# seletor.net
KiCad netlist of a schematic drawn in EAGLE
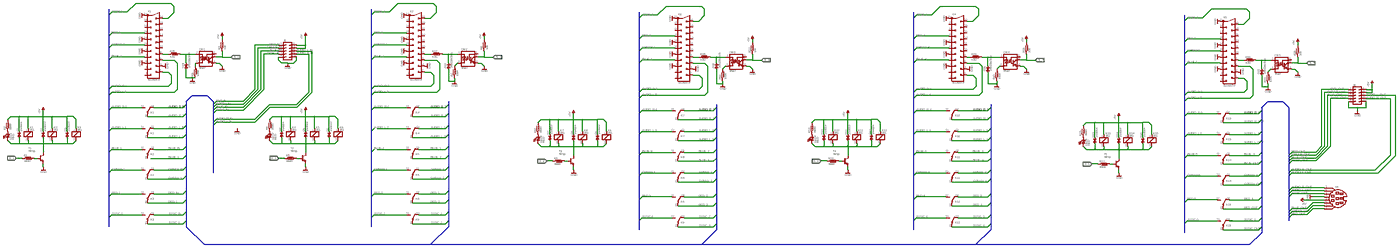
[diagram p0: schematic, sheet 1, overview]
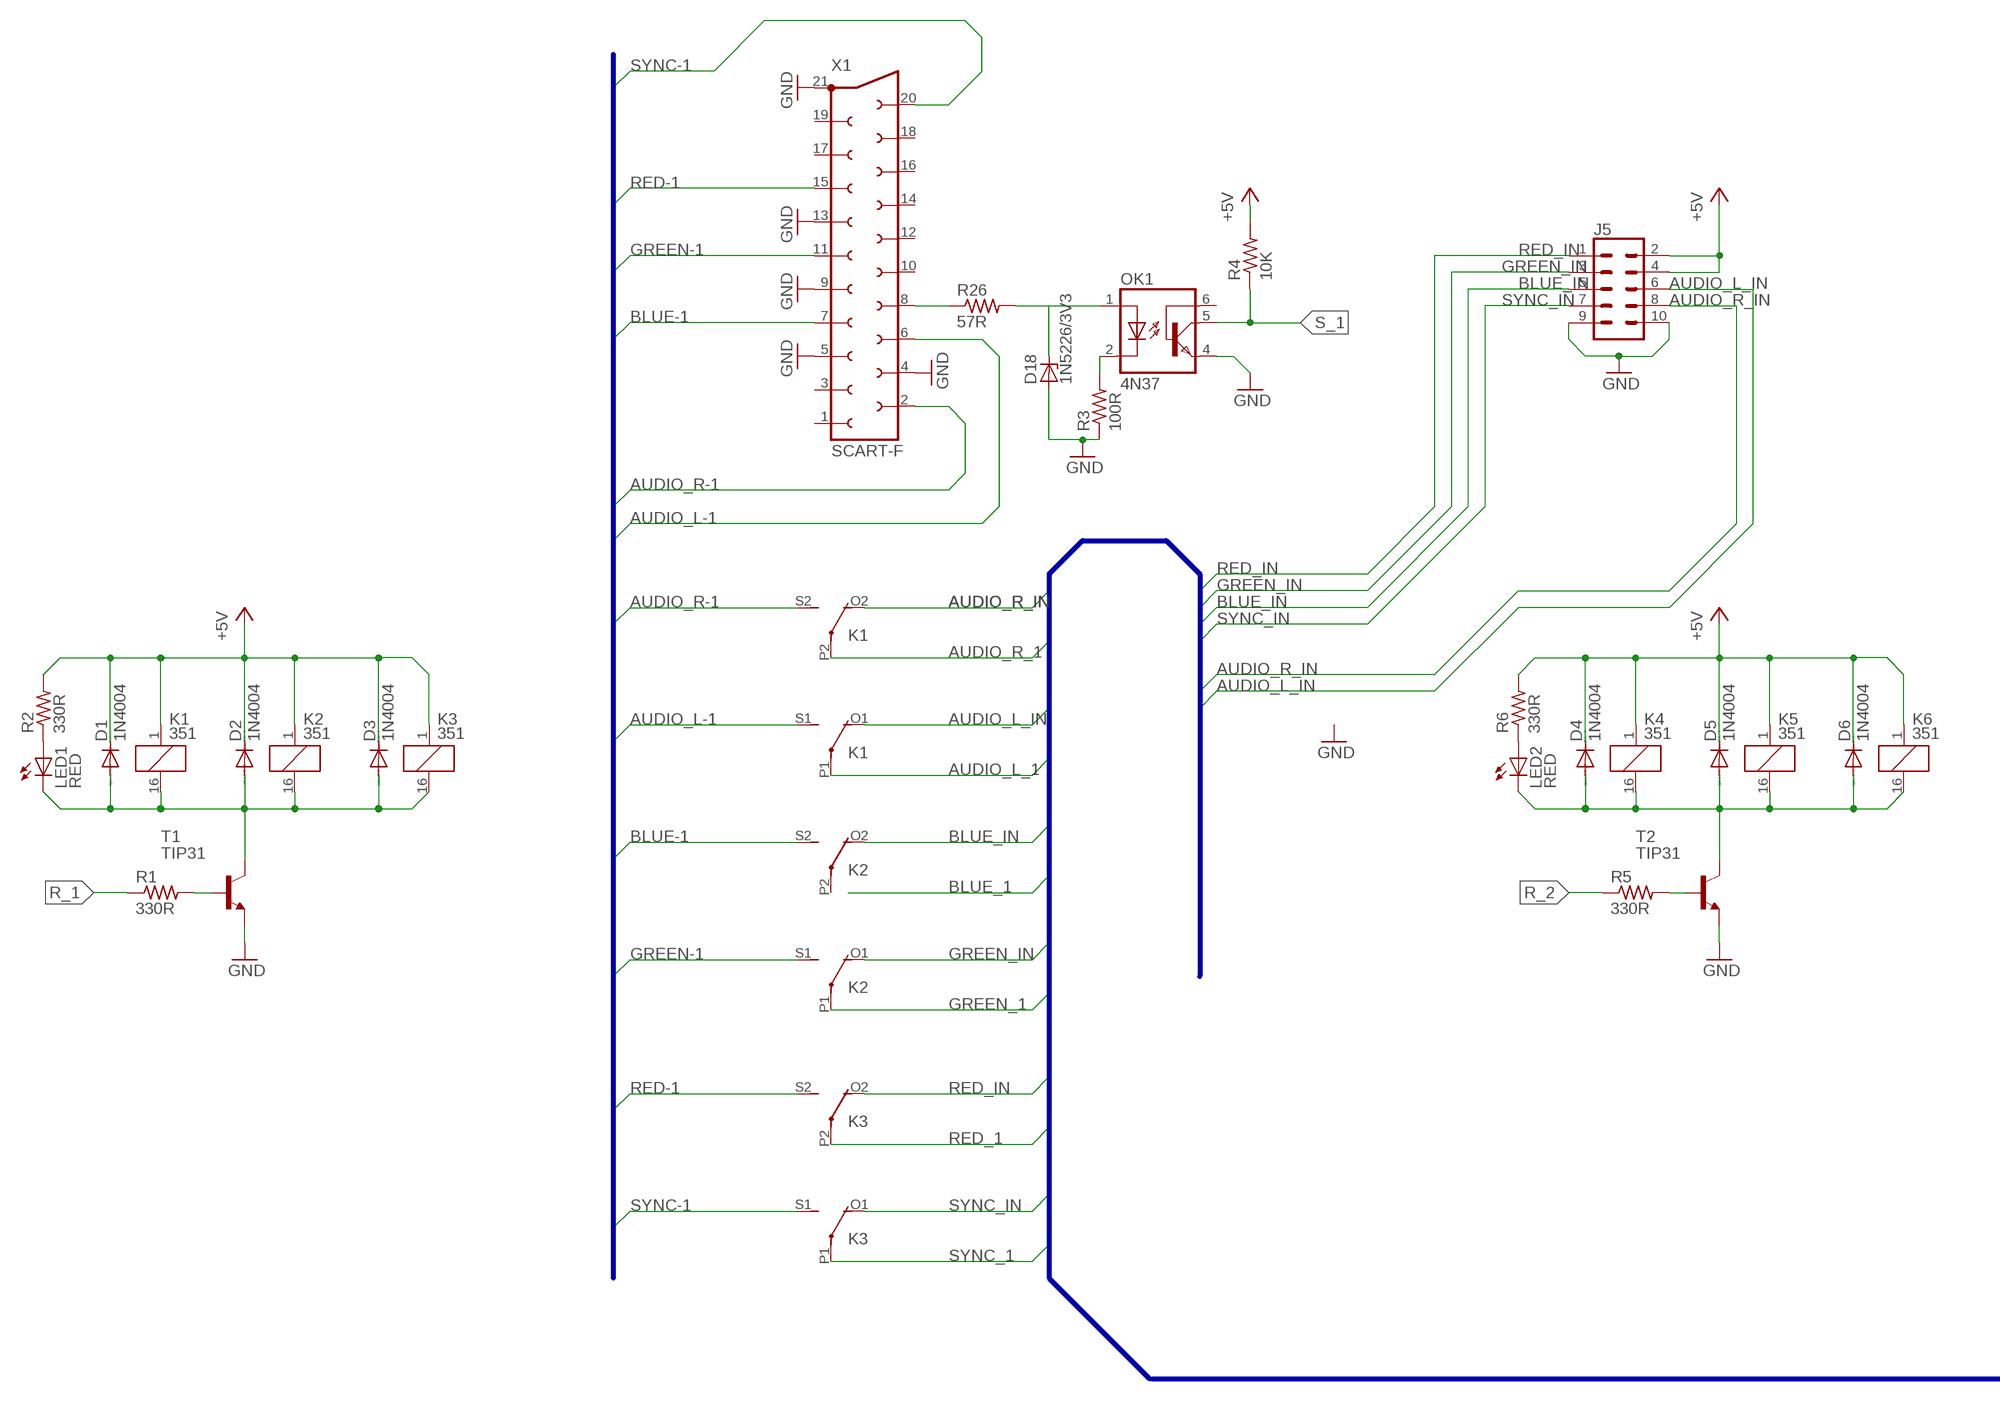
[diagram p1: schematic, sheet 1, part 1 of 4]
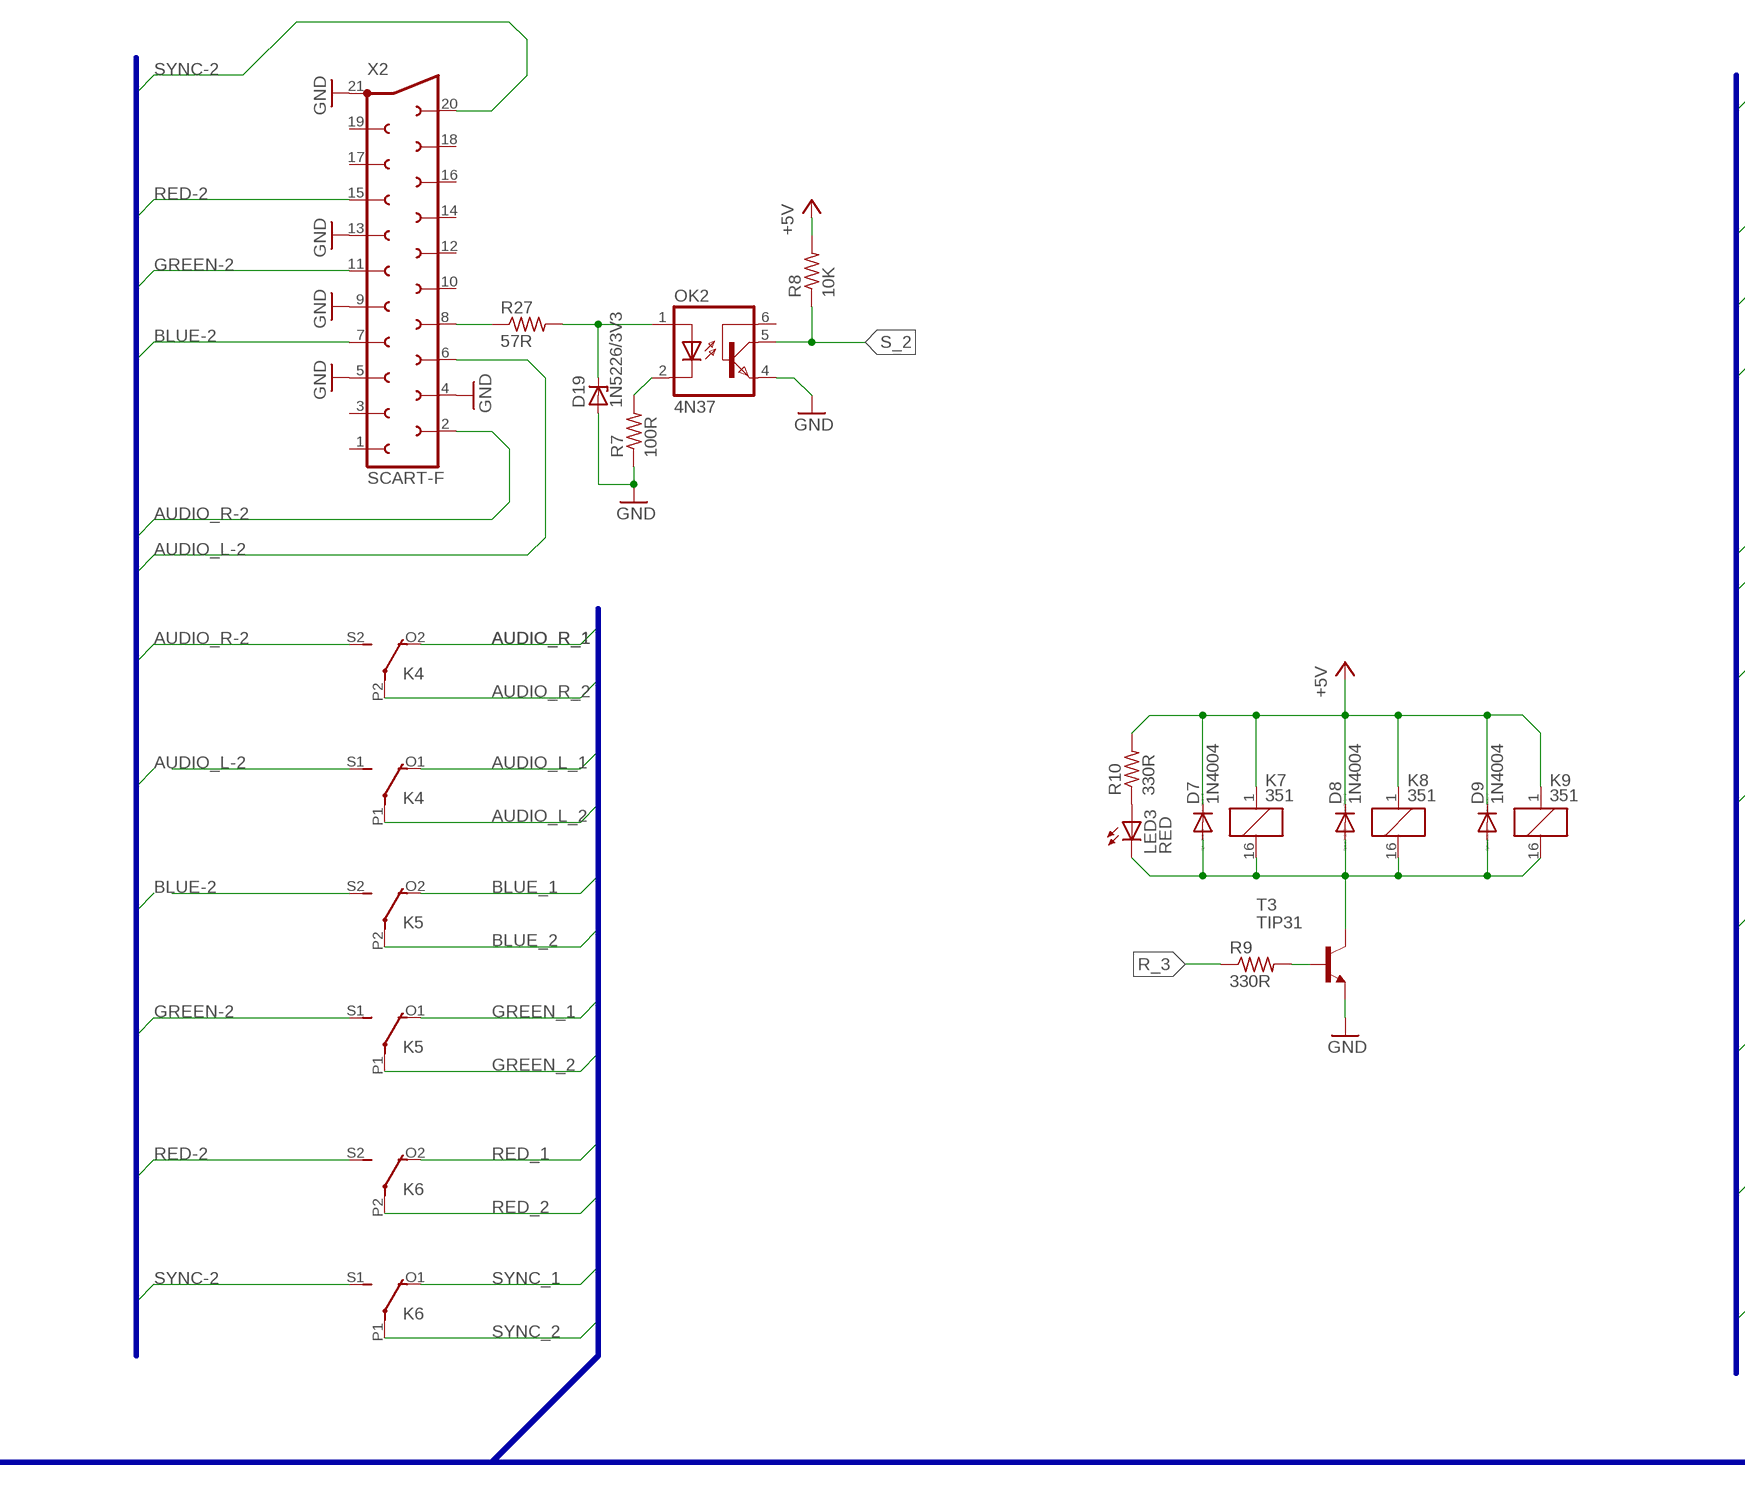
[diagram p2: schematic, sheet 1, part 2 of 4]
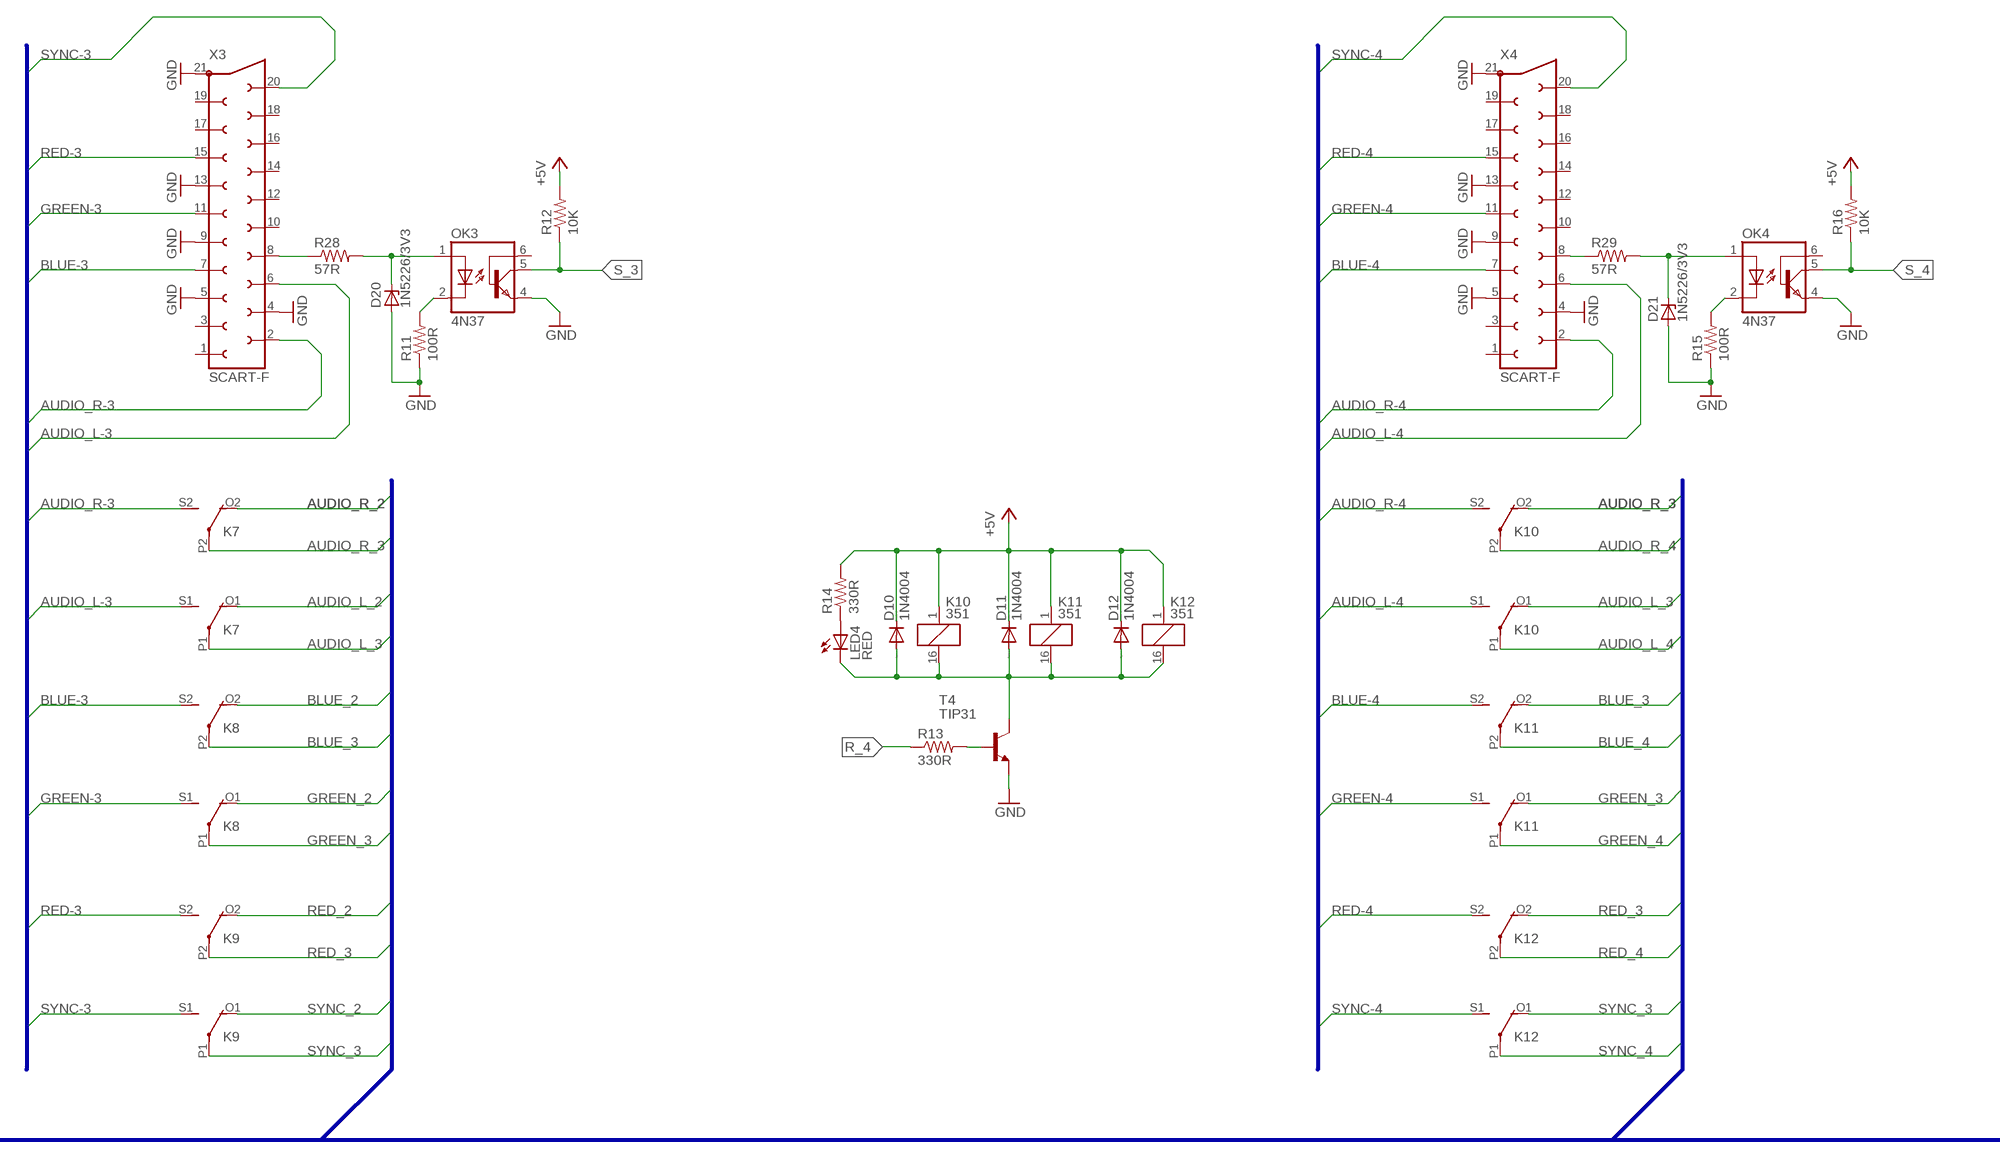
[diagram p3: schematic, sheet 1, part 3 of 4]
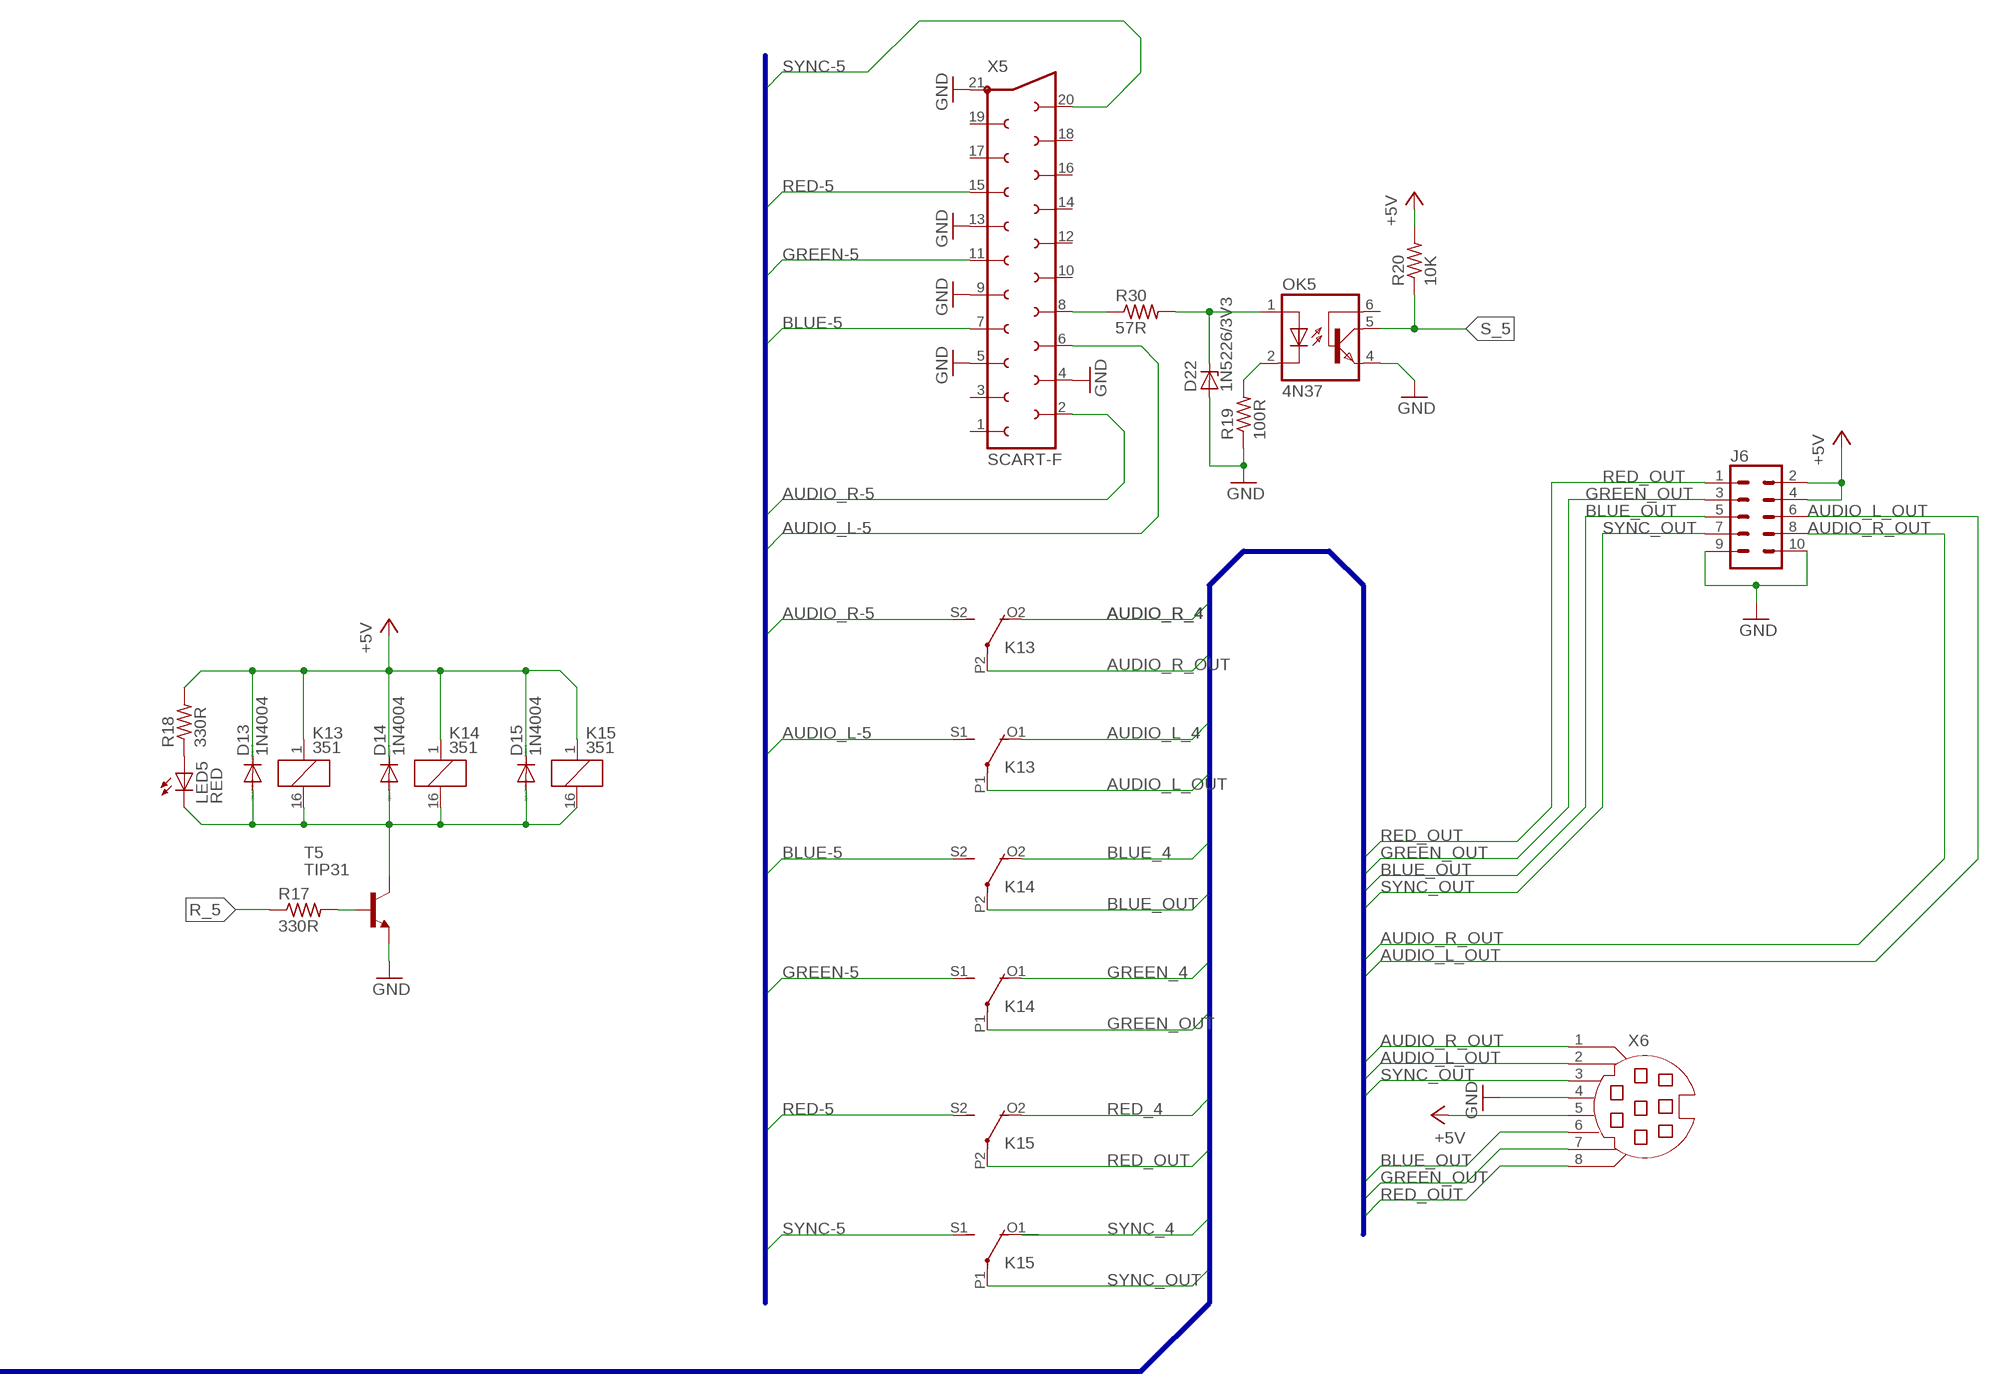
[diagram p4: schematic, sheet 1, part 4 of 4]
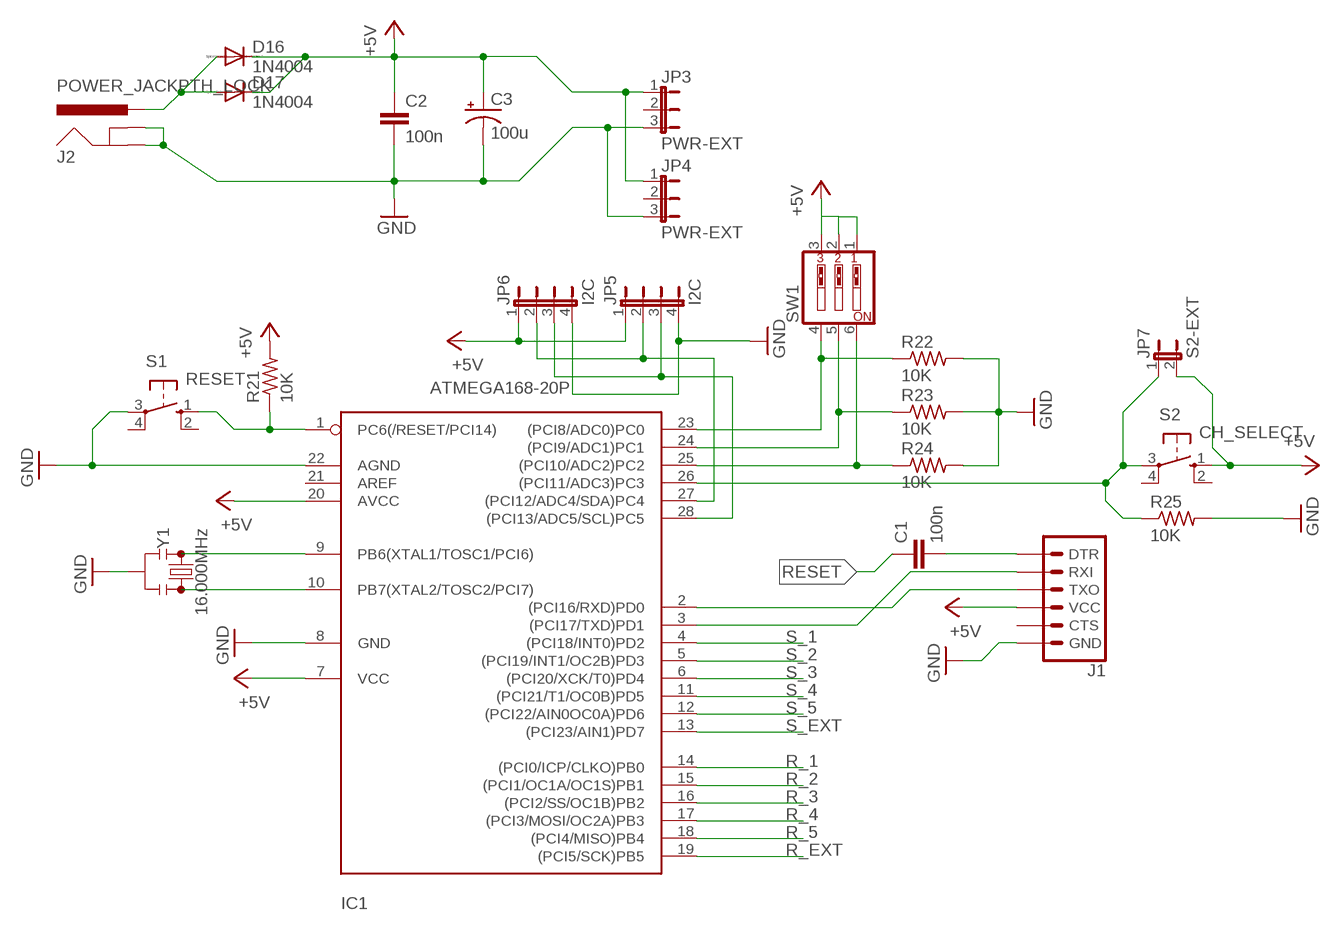
[diagram p5: schematic, sheet 2]

(export (version "E")
  (design (tool "Eeschema 10.0.6"))
  (components
    (comp (ref "D1")
      (value "1N4004")
      (footprint "eagle-import:DO41-10")
      (libsource (lib "eagle-import") (part "1N4004"))
    )
    (comp (ref "D2")
      (value "1N4004")
      (footprint "eagle-import:DO41-10")
      (libsource (lib "eagle-import") (part "1N4004"))
    )
    (comp (ref "D3")
      (value "1N4004")
      (footprint "eagle-import:DO41-10")
      (libsource (lib "eagle-import") (part "1N4004"))
    )
    (comp (ref "D4")
      (value "1N4004")
      (footprint "eagle-import:DO41-10")
      (libsource (lib "eagle-import") (part "1N4004"))
    )
    (comp (ref "D5")
      (value "1N4004")
      (footprint "eagle-import:DO41-10")
      (libsource (lib "eagle-import") (part "1N4004"))
    )
    (comp (ref "D6")
      (value "1N4004")
      (footprint "eagle-import:DO41-10")
      (libsource (lib "eagle-import") (part "1N4004"))
    )
    (comp (ref "D7")
      (value "1N4004")
      (footprint "eagle-import:DO41-10")
      (libsource (lib "eagle-import") (part "1N4004"))
    )
    (comp (ref "D8")
      (value "1N4004")
      (footprint "eagle-import:DO41-10")
      (libsource (lib "eagle-import") (part "1N4004"))
    )
    (comp (ref "D9")
      (value "1N4004")
      (footprint "eagle-import:DO41-10")
      (libsource (lib "eagle-import") (part "1N4004"))
    )
    (comp (ref "D10")
      (value "1N4004")
      (footprint "eagle-import:DO41-10")
      (libsource (lib "eagle-import") (part "1N4004"))
    )
    (comp (ref "D11")
      (value "1N4004")
      (footprint "eagle-import:DO41-10")
      (libsource (lib "eagle-import") (part "1N4004"))
    )
    (comp (ref "D12")
      (value "1N4004")
      (footprint "eagle-import:DO41-10")
      (libsource (lib "eagle-import") (part "1N4004"))
    )
    (comp (ref "D13")
      (value "1N4004")
      (footprint "eagle-import:DO41-10")
      (libsource (lib "eagle-import") (part "1N4004"))
    )
    (comp (ref "D14")
      (value "1N4004")
      (footprint "eagle-import:DO41-10")
      (libsource (lib "eagle-import") (part "1N4004"))
    )
    (comp (ref "D15")
      (value "1N4004")
      (footprint "eagle-import:DO41-10")
      (libsource (lib "eagle-import") (part "1N4004"))
    )
    (comp (ref "D18")
      (value "1N5226/3V3")
      (footprint "eagle-import:DO34Z7")
      (libsource (lib "eagle-import") (part "BZV10"))
    )
    (comp (ref "D19")
      (value "1N5226/3V3")
      (footprint "eagle-import:DO34Z7")
      (libsource (lib "eagle-import") (part "BZV10"))
    )
    (comp (ref "D20")
      (value "1N5226/3V3")
      (footprint "eagle-import:DO34Z7")
      (libsource (lib "eagle-import") (part "BZV10"))
    )
    (comp (ref "D21")
      (value "1N5226/3V3")
      (footprint "eagle-import:DO34Z7")
      (libsource (lib "eagle-import") (part "BZV10"))
    )
    (comp (ref "D22")
      (value "1N5226/3V3")
      (footprint "eagle-import:DO34Z7")
      (libsource (lib "eagle-import") (part "BZV10"))
    )
    (comp (ref "J5")
      (value "CONN_05X2SHD")
      (footprint "eagle-import:2X5-SHROUDED")
      (libsource (lib "eagle-import") (part "CONN_05X2SHD"))
    )
    (comp (ref "J6")
      (value "CONN_05X2SHD")
      (footprint "eagle-import:2X5-SHROUDED")
      (libsource (lib "eagle-import") (part "CONN_05X2SHD"))
    )
    (comp (ref "K1")
      (value "351")
      (footprint "eagle-import:351")
      (libsource (lib "eagle-import") (part "351"))
    )
    (comp (ref "K2")
      (value "351")
      (footprint "eagle-import:351")
      (libsource (lib "eagle-import") (part "351"))
    )
    (comp (ref "K3")
      (value "351")
      (footprint "eagle-import:351")
      (libsource (lib "eagle-import") (part "351"))
    )
    (comp (ref "K4")
      (value "351")
      (footprint "eagle-import:351")
      (libsource (lib "eagle-import") (part "351"))
    )
    (comp (ref "K5")
      (value "351")
      (footprint "eagle-import:351")
      (libsource (lib "eagle-import") (part "351"))
    )
    (comp (ref "K6")
      (value "351")
      (footprint "eagle-import:351")
      (libsource (lib "eagle-import") (part "351"))
    )
    (comp (ref "K7")
      (value "351")
      (footprint "eagle-import:351")
      (libsource (lib "eagle-import") (part "351"))
    )
    (comp (ref "K8")
      (value "351")
      (footprint "eagle-import:351")
      (libsource (lib "eagle-import") (part "351"))
    )
    (comp (ref "K9")
      (value "351")
      (footprint "eagle-import:351")
      (libsource (lib "eagle-import") (part "351"))
    )
    (comp (ref "K10")
      (value "351")
      (footprint "eagle-import:351")
      (libsource (lib "eagle-import") (part "351"))
    )
    (comp (ref "K11")
      (value "351")
      (footprint "eagle-import:351")
      (libsource (lib "eagle-import") (part "351"))
    )
    (comp (ref "K12")
      (value "351")
      (footprint "eagle-import:351")
      (libsource (lib "eagle-import") (part "351"))
    )
    (comp (ref "K13")
      (value "351")
      (footprint "eagle-import:351")
      (libsource (lib "eagle-import") (part "351"))
    )
    (comp (ref "K14")
      (value "351")
      (footprint "eagle-import:351")
      (libsource (lib "eagle-import") (part "351"))
    )
    (comp (ref "K15")
      (value "351")
      (footprint "eagle-import:351")
      (libsource (lib "eagle-import") (part "351"))
    )
    (comp (ref "LED1")
      (value "RED")
      (footprint "eagle-import:LED5MM")
      (libsource (lib "eagle-import") (part "LED5MM"))
    )
    (comp (ref "LED2")
      (value "RED")
      (footprint "eagle-import:LED5MM")
      (libsource (lib "eagle-import") (part "LED5MM"))
    )
    (comp (ref "LED3")
      (value "RED")
      (footprint "eagle-import:LED5MM")
      (libsource (lib "eagle-import") (part "LED5MM"))
    )
    (comp (ref "LED4")
      (value "RED")
      (footprint "eagle-import:LED5MM")
      (libsource (lib "eagle-import") (part "LED5MM"))
    )
    (comp (ref "LED5")
      (value "RED")
      (footprint "eagle-import:LED5MM")
      (libsource (lib "eagle-import") (part "LED5MM"))
    )
    (comp (ref "OK1")
      (value "4N37")
      (footprint "eagle-import:DIL06")
      (fields (field (name "MF") "FAIRCHILD SEMICONDUCTOR"))
      (libsource (lib "eagle-import") (part "4N37"))
    )
    (comp (ref "OK2")
      (value "4N37")
      (footprint "eagle-import:DIL06")
      (fields (field (name "MF") "FAIRCHILD SEMICONDUCTOR"))
      (libsource (lib "eagle-import") (part "4N37"))
    )
    (comp (ref "OK3")
      (value "4N37")
      (footprint "eagle-import:DIL06")
      (fields (field (name "MF") "FAIRCHILD SEMICONDUCTOR"))
      (libsource (lib "eagle-import") (part "4N37"))
    )
    (comp (ref "OK4")
      (value "4N37")
      (footprint "eagle-import:DIL06")
      (fields (field (name "MF") "FAIRCHILD SEMICONDUCTOR"))
      (libsource (lib "eagle-import") (part "4N37"))
    )
    (comp (ref "OK5")
      (value "4N37")
      (footprint "eagle-import:DIL06")
      (fields (field (name "MF") "FAIRCHILD SEMICONDUCTOR"))
      (libsource (lib "eagle-import") (part "4N37"))
    )
    (comp (ref "R1")
      (value "330R")
      (footprint "eagle-import:0204_7")
      (libsource (lib "eagle-import") (part "R-US_0204/7"))
    )
    (comp (ref "R2")
      (value "330R")
      (footprint "eagle-import:0204V")
      (libsource (lib "eagle-import") (part "R-US_0204/2V"))
    )
    (comp (ref "R3")
      (value "100R")
      (footprint "eagle-import:0204V")
      (libsource (lib "eagle-import") (part "R-US_0204/2V"))
    )
    (comp (ref "R4")
      (value "10K")
      (footprint "eagle-import:0204V")
      (libsource (lib "eagle-import") (part "R-US_0204/2V"))
    )
    (comp (ref "R5")
      (value "330R")
      (footprint "eagle-import:0204_7")
      (libsource (lib "eagle-import") (part "R-US_0204/7"))
    )
    (comp (ref "R6")
      (value "330R")
      (footprint "eagle-import:0204V")
      (libsource (lib "eagle-import") (part "R-US_0204/2V"))
    )
    (comp (ref "R7")
      (value "100R")
      (footprint "eagle-import:0204V")
      (libsource (lib "eagle-import") (part "R-US_0204/2V"))
    )
    (comp (ref "R8")
      (value "10K")
      (footprint "eagle-import:0204V")
      (libsource (lib "eagle-import") (part "R-US_0204/2V"))
    )
    (comp (ref "R9")
      (value "330R")
      (footprint "eagle-import:0204_7")
      (libsource (lib "eagle-import") (part "R-US_0204/7"))
    )
    (comp (ref "R10")
      (value "330R")
      (footprint "eagle-import:0204V")
      (libsource (lib "eagle-import") (part "R-US_0204/2V"))
    )
    (comp (ref "R11")
      (value "100R")
      (footprint "eagle-import:0204V")
      (libsource (lib "eagle-import") (part "R-US_0204/2V"))
    )
    (comp (ref "R12")
      (value "10K")
      (footprint "eagle-import:0204V")
      (libsource (lib "eagle-import") (part "R-US_0204/2V"))
    )
    (comp (ref "R13")
      (value "330R")
      (footprint "eagle-import:0204_7")
      (libsource (lib "eagle-import") (part "R-US_0204/7"))
    )
    (comp (ref "R14")
      (value "330R")
      (footprint "eagle-import:0204V")
      (libsource (lib "eagle-import") (part "R-US_0204/2V"))
    )
    (comp (ref "R15")
      (value "100R")
      (footprint "eagle-import:0204V")
      (libsource (lib "eagle-import") (part "R-US_0204/2V"))
    )
    (comp (ref "R16")
      (value "10K")
      (footprint "eagle-import:0204V")
      (libsource (lib "eagle-import") (part "R-US_0204/2V"))
    )
    (comp (ref "R17")
      (value "330R")
      (footprint "eagle-import:0204_7")
      (libsource (lib "eagle-import") (part "R-US_0204/7"))
    )
    (comp (ref "R18")
      (value "330R")
      (footprint "eagle-import:0204V")
      (libsource (lib "eagle-import") (part "R-US_0204/2V"))
    )
    (comp (ref "R19")
      (value "100R")
      (footprint "eagle-import:0204V")
      (libsource (lib "eagle-import") (part "R-US_0204/2V"))
    )
    (comp (ref "R20")
      (value "10K")
      (footprint "eagle-import:0204V")
      (libsource (lib "eagle-import") (part "R-US_0204/2V"))
    )
    (comp (ref "R26")
      (value "57R")
      (footprint "eagle-import:0204_7")
      (libsource (lib "eagle-import") (part "resistor_R-US_0204/7"))
    )
    (comp (ref "R27")
      (value "57R")
      (footprint "eagle-import:0204_7")
      (libsource (lib "eagle-import") (part "resistor_R-US_0204/7"))
    )
    (comp (ref "R28")
      (value "57R")
      (footprint "eagle-import:0204_7")
      (libsource (lib "eagle-import") (part "resistor_R-US_0204/7"))
    )
    (comp (ref "R29")
      (value "57R")
      (footprint "eagle-import:0204_7")
      (libsource (lib "eagle-import") (part "resistor_R-US_0204/7"))
    )
    (comp (ref "R30")
      (value "57R")
      (footprint "eagle-import:0204_7")
      (libsource (lib "eagle-import") (part "resistor_R-US_0204/7"))
    )
    (comp (ref "T1")
      (value "TIP31")
      (footprint "eagle-import:TO220")
      (libsource (lib "eagle-import") (part "TIP31"))
    )
    (comp (ref "T2")
      (value "TIP31")
      (footprint "eagle-import:TO220")
      (libsource (lib "eagle-import") (part "TIP31"))
    )
    (comp (ref "T3")
      (value "TIP31")
      (footprint "eagle-import:TO220")
      (libsource (lib "eagle-import") (part "TIP31"))
    )
    (comp (ref "T4")
      (value "TIP31")
      (footprint "eagle-import:TO220")
      (libsource (lib "eagle-import") (part "TIP31"))
    )
    (comp (ref "T5")
      (value "TIP31")
      (footprint "eagle-import:TO220")
      (libsource (lib "eagle-import") (part "TIP31"))
    )
    (comp (ref "X1")
      (value "SCART-F")
      (footprint "eagle-import:SCART-F")
      (libsource (lib "eagle-import") (part "SCART-F"))
    )
    (comp (ref "X2")
      (value "SCART-F")
      (footprint "eagle-import:SCART-F")
      (libsource (lib "eagle-import") (part "SCART-F"))
    )
    (comp (ref "X3")
      (value "SCART-F")
      (footprint "eagle-import:SCART-F")
      (libsource (lib "eagle-import") (part "SCART-F"))
    )
    (comp (ref "X4")
      (value "SCART-F")
      (footprint "eagle-import:SCART-F")
      (libsource (lib "eagle-import") (part "SCART-F"))
    )
    (comp (ref "X5")
      (value "SCART-F")
      (footprint "eagle-import:SCART-F")
      (libsource (lib "eagle-import") (part "SCART-F"))
    )
    (comp (ref "X6")
      (value "MD08SS")
      (footprint "eagle-import:MDIN08SS")
      (libsource (lib "eagle-import") (part "MD08SS"))
    )
    (comp (ref "C1")
      (value "100n")
      (footprint "eagle-import:C7.5B3")
      (libsource (lib "eagle-import") (part "C7.5/3"))
    )
    (comp (ref "C2")
      (value "100n")
      (footprint "eagle-import:C7.5B3")
      (libsource (lib "eagle-import") (part "C7.5/3"))
    )
    (comp (ref "C3")
      (value "100u")
      (footprint "eagle-import:E3,5-10")
      (libsource (lib "eagle-import") (part "CPOL-USE3.5-10"))
    )
    (comp (ref "D16")
      (value "1N4004")
      (footprint "eagle-import:DO41-10")
      (libsource (lib "eagle-import") (part "1N4004"))
    )
    (comp (ref "D17")
      (value "1N4004")
      (footprint "eagle-import:DO41-10")
      (libsource (lib "eagle-import") (part "1N4004"))
    )
    (comp (ref "IC1")
      (value "ATMEGA168-20P")
      (footprint "eagle-import:DIL28-3")
      (libsource (lib "eagle-import") (part "ATMEGA168P-20"))
    )
    (comp (ref "J1")
      (value "6_PIN_SERIAL_TARGETSILK")
      (footprint "eagle-import:6_PIN_SERIAL_TARGET_SIDE_W_SILK")
      (libsource (lib "eagle-import") (part "6_PIN_SERIAL_TARGETSILK"))
    )
    (comp (ref "J2")
      (value "POWER_JACKPTH_LOCK")
      (footprint "eagle-import:POWER_JACK_PTH_LOCK")
      (libsource (lib "eagle-import") (part "POWER_JACKPTH_LOCK"))
    )
    (comp (ref "JP3")
      (value "PWR-EXT")
      (footprint "eagle-import:JP2")
      (libsource (lib "eagle-import") (part "JP2E"))
    )
    (comp (ref "JP4")
      (value "PWR-EXT")
      (footprint "eagle-import:JP2")
      (libsource (lib "eagle-import") (part "JP2E"))
    )
    (comp (ref "JP5")
      (value "I2C")
      (footprint "eagle-import:JP4")
      (libsource (lib "eagle-import") (part "JP4E"))
    )
    (comp (ref "JP6")
      (value "I2C")
      (footprint "eagle-import:JP4")
      (libsource (lib "eagle-import") (part "JP4E"))
    )
    (comp (ref "JP7")
      (value "S2-EXT")
      (footprint "eagle-import:JP1")
      (libsource (lib "eagle-import") (part "JP1E"))
    )
    (comp (ref "R21")
      (value "10K")
      (footprint "eagle-import:0204_7")
      (libsource (lib "eagle-import") (part "R-US_0204/7"))
    )
    (comp (ref "R22")
      (value "10K")
      (footprint "eagle-import:0204_7")
      (libsource (lib "eagle-import") (part "R-US_0204/7"))
    )
    (comp (ref "R23")
      (value "10K")
      (footprint "eagle-import:0204_7")
      (libsource (lib "eagle-import") (part "R-US_0204/7"))
    )
    (comp (ref "R24")
      (value "10K")
      (footprint "eagle-import:0204_7")
      (libsource (lib "eagle-import") (part "R-US_0204/7"))
    )
    (comp (ref "R25")
      (value "10K")
      (footprint "eagle-import:0204_7")
      (libsource (lib "eagle-import") (part "R-US_0204/7"))
    )
    (comp (ref "S1")
      (value "RESET")
      (footprint "eagle-import:B3F-10XX")
      (fields (field (name "MPN") "B3F-1000"))
      (libsource (lib "eagle-import") (part "10-XX"))
    )
    (comp (ref "S2")
      (value "CH_SELECT")
      (footprint "eagle-import:B3F-10XX")
      (fields (field (name "MPN") "B3F-1000"))
      (libsource (lib "eagle-import") (part "10-XX"))
    )
    (comp (ref "SW1")
      (value "SW_DIP-3")
      (footprint "eagle-import:EDG-03")
      (libsource (lib "eagle-import") (part "SW_DIP-3"))
    )
    (comp (ref "Y1")
      (value "16.000MHz")
      (footprint "eagle-import:RESONATOR-PTH-7.6X3.8")
      (libsource (lib "eagle-import") (part "RESONATORPTH-7.6X3.8"))
    )
  )
  (nets
    (net (code "2") (name "+5V") (class "Default")
      (node (ref "C2") (pin "1") (pinfunction "1_1") (pintype "passive"))
      (node (ref "C3") (pin "+") (pinfunction "+_+") (pintype "passive"))
      (node (ref "D1") (pin "C") (pinfunction "C_C") (pintype "passive"))
      (node (ref "D10") (pin "C") (pinfunction "C_C") (pintype "passive"))
      (node (ref "D11") (pin "C") (pinfunction "C_C") (pintype "passive"))
      (node (ref "D12") (pin "C") (pinfunction "C_C") (pintype "passive"))
      (node (ref "D13") (pin "C") (pinfunction "C_C") (pintype "passive"))
      (node (ref "D14") (pin "C") (pinfunction "C_C") (pintype "passive"))
      (node (ref "D15") (pin "C") (pinfunction "C_C") (pintype "passive"))
      (node (ref "D16") (pin "C") (pinfunction "C_C") (pintype "passive"))
      (node (ref "D17") (pin "C") (pinfunction "C_C") (pintype "passive"))
      (node (ref "D2") (pin "C") (pinfunction "C_C") (pintype "passive"))
      (node (ref "D3") (pin "C") (pinfunction "C_C") (pintype "passive"))
      (node (ref "D4") (pin "C") (pinfunction "C_C") (pintype "passive"))
      (node (ref "D5") (pin "C") (pinfunction "C_C") (pintype "passive"))
      (node (ref "D6") (pin "C") (pinfunction "C_C") (pintype "passive"))
      (node (ref "D7") (pin "C") (pinfunction "C_C") (pintype "passive"))
      (node (ref "D8") (pin "C") (pinfunction "C_C") (pintype "passive"))
      (node (ref "D9") (pin "C") (pinfunction "C_C") (pintype "passive"))
      (node (ref "IC1") (pin "20") (pinfunction "AVCC_20") (pintype "bidirectional"))
      (node (ref "IC1") (pin "7") (pinfunction "VCC_7") (pintype "bidirectional"))
      (node (ref "J1") (pin "P$4") (pinfunction "VCC_P$4") (pintype "passive"))
      (node (ref "J5") (pin "2") (pinfunction "2_2") (pintype "passive"))
      (node (ref "J5") (pin "4") (pinfunction "4_4") (pintype "passive"))
      (node (ref "J6") (pin "2") (pinfunction "2_2") (pintype "passive"))
      (node (ref "J6") (pin "4") (pinfunction "4_4") (pintype "passive"))
      (node (ref "JP3") (pin "1") (pinfunction "1_1") (pintype "passive"))
      (node (ref "JP4") (pin "1") (pinfunction "1_1") (pintype "passive"))
      (node (ref "JP5") (pin "1") (pinfunction "1_1") (pintype "passive"))
      (node (ref "JP6") (pin "1") (pinfunction "1_1") (pintype "passive"))
      (node (ref "JP7") (pin "2") (pinfunction "2_2") (pintype "passive"))
      (node (ref "K1") (pin "1") (pinfunction "1_1") (pintype "passive"))
      (node (ref "K10") (pin "1") (pinfunction "1_1") (pintype "passive"))
      (node (ref "K11") (pin "1") (pinfunction "1_1") (pintype "passive"))
      (node (ref "K12") (pin "1") (pinfunction "1_1") (pintype "passive"))
      (node (ref "K13") (pin "1") (pinfunction "1_1") (pintype "passive"))
      (node (ref "K14") (pin "1") (pinfunction "1_1") (pintype "passive"))
      (node (ref "K15") (pin "1") (pinfunction "1_1") (pintype "passive"))
      (node (ref "K2") (pin "1") (pinfunction "1_1") (pintype "passive"))
      (node (ref "K3") (pin "1") (pinfunction "1_1") (pintype "passive"))
      (node (ref "K4") (pin "1") (pinfunction "1_1") (pintype "passive"))
      (node (ref "K5") (pin "1") (pinfunction "1_1") (pintype "passive"))
      (node (ref "K6") (pin "1") (pinfunction "1_1") (pintype "passive"))
      (node (ref "K7") (pin "1") (pinfunction "1_1") (pintype "passive"))
      (node (ref "K8") (pin "1") (pinfunction "1_1") (pintype "passive"))
      (node (ref "K9") (pin "1") (pinfunction "1_1") (pintype "passive"))
      (node (ref "R10") (pin "2") (pinfunction "2_2") (pintype "passive"))
      (node (ref "R12") (pin "2") (pinfunction "2_2") (pintype "passive"))
      (node (ref "R14") (pin "2") (pinfunction "2_2") (pintype "passive"))
      (node (ref "R16") (pin "2") (pinfunction "2_2") (pintype "passive"))
      (node (ref "R18") (pin "2") (pinfunction "2_2") (pintype "passive"))
      (node (ref "R2") (pin "2") (pinfunction "2_2") (pintype "passive"))
      (node (ref "R20") (pin "2") (pinfunction "2_2") (pintype "passive"))
      (node (ref "R21") (pin "2") (pinfunction "2_2") (pintype "passive"))
      (node (ref "R4") (pin "2") (pinfunction "2_2") (pintype "passive"))
      (node (ref "R6") (pin "2") (pinfunction "2_2") (pintype "passive"))
      (node (ref "R8") (pin "2") (pinfunction "2_2") (pintype "passive"))
      (node (ref "S2") (pin "1") (pinfunction "S_1") (pintype "passive"))
      (node (ref "SW1") (pin "1") (pinfunction "1_1") (pintype "passive"))
      (node (ref "SW1") (pin "2") (pinfunction "2_2") (pintype "passive"))
      (node (ref "SW1") (pin "3") (pinfunction "3_3") (pintype "passive"))
      (node (ref "X6") (pin "5") (pinfunction "5_5") (pintype "passive"))
    )
    (net (code "4") (name "AUDIO_L-1") (class "Default")
      (node (ref "K1") (pin "S1") (pinfunction "S_S1") (pintype "passive"))
      (node (ref "X1") (pin "6") (pinfunction "6_6") (pintype "passive"))
    )
    (net (code "5") (name "AUDIO_L-2") (class "Default")
      (node (ref "X2") (pin "6") (pinfunction "6_6") (pintype "passive"))
    )
    (net (code "6") (name "AUDIO_L-3") (class "Default")
      (node (ref "K7") (pin "S1") (pinfunction "S_S1") (pintype "passive"))
      (node (ref "X3") (pin "6") (pinfunction "6_6") (pintype "passive"))
    )
    (net (code "7") (name "AUDIO_L-4") (class "Default")
      (node (ref "K10") (pin "S1") (pinfunction "S_S1") (pintype "passive"))
      (node (ref "X4") (pin "6") (pinfunction "6_6") (pintype "passive"))
    )
    (net (code "8") (name "AUDIO_L-5") (class "Default")
      (node (ref "K13") (pin "S1") (pinfunction "S_S1") (pintype "passive"))
      (node (ref "X5") (pin "6") (pinfunction "6_6") (pintype "passive"))
    )
    (net (code "9") (name "AUDIO_L_1") (class "Default")
      (node (ref "K1") (pin "P1") (pinfunction "P_P1") (pintype "passive"))
      (node (ref "K4") (pin "O1") (pinfunction "O_O1") (pintype "passive"))
    )
    (net (code "10") (name "AUDIO_L_2") (class "Default")
      (node (ref "K4") (pin "P1") (pinfunction "P_P1") (pintype "passive"))
      (node (ref "K7") (pin "O1") (pinfunction "O_O1") (pintype "passive"))
    )
    (net (code "11") (name "AUDIO_L_3") (class "Default")
      (node (ref "K10") (pin "O1") (pinfunction "O_O1") (pintype "passive"))
      (node (ref "K7") (pin "P1") (pinfunction "P_P1") (pintype "passive"))
    )
    (net (code "12") (name "AUDIO_L_4") (class "Default")
      (node (ref "K10") (pin "P1") (pinfunction "P_P1") (pintype "passive"))
      (node (ref "K13") (pin "O1") (pinfunction "O_O1") (pintype "passive"))
    )
    (net (code "13") (name "AUDIO_L_IN") (class "Default")
      (node (ref "J5") (pin "6") (pinfunction "6_6") (pintype "passive"))
      (node (ref "K1") (pin "O1") (pinfunction "O_O1") (pintype "passive"))
    )
    (net (code "14") (name "AUDIO_L_OUT") (class "Default")
      (node (ref "J6") (pin "6") (pinfunction "6_6") (pintype "passive"))
      (node (ref "K13") (pin "P1") (pinfunction "P_P1") (pintype "passive"))
      (node (ref "X6") (pin "2") (pinfunction "2_2") (pintype "passive"))
    )
    (net (code "15") (name "AUDIO_R-1") (class "Default")
      (node (ref "K1") (pin "S2") (pinfunction "S_S2") (pintype "passive"))
      (node (ref "X1") (pin "2") (pinfunction "2_2") (pintype "passive"))
    )
    (net (code "16") (name "AUDIO_R-2") (class "Default")
      (node (ref "K4") (pin "S2") (pinfunction "S_S2") (pintype "passive"))
      (node (ref "X2") (pin "2") (pinfunction "2_2") (pintype "passive"))
    )
    (net (code "17") (name "AUDIO_R-3") (class "Default")
      (node (ref "K7") (pin "S2") (pinfunction "S_S2") (pintype "passive"))
      (node (ref "X3") (pin "2") (pinfunction "2_2") (pintype "passive"))
    )
    (net (code "18") (name "AUDIO_R-4") (class "Default")
      (node (ref "K10") (pin "S2") (pinfunction "S_S2") (pintype "passive"))
      (node (ref "X4") (pin "2") (pinfunction "2_2") (pintype "passive"))
    )
    (net (code "19") (name "AUDIO_R-5") (class "Default")
      (node (ref "K13") (pin "S2") (pinfunction "S_S2") (pintype "passive"))
      (node (ref "X5") (pin "2") (pinfunction "2_2") (pintype "passive"))
    )
    (net (code "20") (name "AUDIO_R_1") (class "Default")
      (node (ref "K1") (pin "P2") (pinfunction "P_P2") (pintype "passive"))
      (node (ref "K4") (pin "O2") (pinfunction "O_O2") (pintype "passive"))
    )
    (net (code "21") (name "AUDIO_R_2") (class "Default")
      (node (ref "K4") (pin "P2") (pinfunction "P_P2") (pintype "passive"))
      (node (ref "K7") (pin "O2") (pinfunction "O_O2") (pintype "passive"))
    )
    (net (code "22") (name "AUDIO_R_3") (class "Default")
      (node (ref "K10") (pin "O2") (pinfunction "O_O2") (pintype "passive"))
      (node (ref "K7") (pin "P2") (pinfunction "P_P2") (pintype "passive"))
    )
    (net (code "23") (name "AUDIO_R_4") (class "Default")
      (node (ref "K10") (pin "P2") (pinfunction "P_P2") (pintype "passive"))
      (node (ref "K13") (pin "O2") (pinfunction "O_O2") (pintype "passive"))
    )
    (net (code "24") (name "AUDIO_R_IN") (class "Default")
      (node (ref "J5") (pin "8") (pinfunction "8_8") (pintype "passive"))
      (node (ref "K1") (pin "O2") (pinfunction "O_O2") (pintype "passive"))
    )
    (net (code "25") (name "AUDIO_R_OUT") (class "Default")
      (node (ref "J6") (pin "8") (pinfunction "8_8") (pintype "passive"))
      (node (ref "K13") (pin "P2") (pinfunction "P_P2") (pintype "passive"))
      (node (ref "X6") (pin "1") (pinfunction "1_1") (pintype "passive"))
    )
    (net (code "26") (name "BLUE-1") (class "Default")
      (node (ref "K2") (pin "S2") (pinfunction "S_S2") (pintype "passive"))
      (node (ref "X1") (pin "7") (pinfunction "7_7") (pintype "passive"))
    )
    (net (code "27") (name "BLUE-2") (class "Default")
      (node (ref "X2") (pin "7") (pinfunction "7_7") (pintype "passive"))
    )
    (net (code "28") (name "BLUE-3") (class "Default")
      (node (ref "K8") (pin "S2") (pinfunction "S_S2") (pintype "passive"))
      (node (ref "X3") (pin "7") (pinfunction "7_7") (pintype "passive"))
    )
    (net (code "29") (name "BLUE-4") (class "Default")
      (node (ref "K11") (pin "S2") (pinfunction "S_S2") (pintype "passive"))
      (node (ref "X4") (pin "7") (pinfunction "7_7") (pintype "passive"))
    )
    (net (code "30") (name "BLUE-5") (class "Default")
      (node (ref "K14") (pin "S2") (pinfunction "S_S2") (pintype "passive"))
      (node (ref "X5") (pin "7") (pinfunction "7_7") (pintype "passive"))
    )
    (net (code "31") (name "BLUE_1") (class "Default")
      (node (ref "K5") (pin "O2") (pinfunction "O_O2") (pintype "passive"))
    )
    (net (code "32") (name "BLUE_2") (class "Default")
      (node (ref "K5") (pin "P2") (pinfunction "P_P2") (pintype "passive"))
      (node (ref "K8") (pin "O2") (pinfunction "O_O2") (pintype "passive"))
    )
    (net (code "33") (name "BLUE_3") (class "Default")
      (node (ref "K11") (pin "O2") (pinfunction "O_O2") (pintype "passive"))
      (node (ref "K8") (pin "P2") (pinfunction "P_P2") (pintype "passive"))
    )
    (net (code "34") (name "BLUE_4") (class "Default")
      (node (ref "K11") (pin "P2") (pinfunction "P_P2") (pintype "passive"))
      (node (ref "K14") (pin "O2") (pinfunction "O_O2") (pintype "passive"))
    )
    (net (code "35") (name "BLUE_IN") (class "Default")
      (node (ref "J5") (pin "5") (pinfunction "5_5") (pintype "passive"))
      (node (ref "K2") (pin "O2") (pinfunction "O_O2") (pintype "passive"))
    )
    (net (code "36") (name "BLUE_OUT") (class "Default")
      (node (ref "J6") (pin "5") (pinfunction "5_5") (pintype "passive"))
      (node (ref "K14") (pin "P2") (pinfunction "P_P2") (pintype "passive"))
      (node (ref "X6") (pin "6") (pinfunction "6_6") (pintype "passive"))
    )
    (net (code "37") (name "GND") (class "Default")
      (node (ref "C2") (pin "2") (pinfunction "2_2") (pintype "passive"))
      (node (ref "C3") (pin "-") (pinfunction "-_-") (pintype "passive"))
      (node (ref "D18") (pin "A") (pinfunction "A_A") (pintype "passive"))
      (node (ref "D19") (pin "A") (pinfunction "A_A") (pintype "passive"))
      (node (ref "D20") (pin "A") (pinfunction "A_A") (pintype "passive"))
      (node (ref "D21") (pin "A") (pinfunction "A_A") (pintype "passive"))
      (node (ref "D22") (pin "A") (pinfunction "A_A") (pintype "passive"))
      (node (ref "IC1") (pin "22") (pinfunction "AGND_22") (pintype "bidirectional"))
      (node (ref "IC1") (pin "8") (pinfunction "GND_8") (pintype "bidirectional"))
      (node (ref "J1") (pin "P$6") (pinfunction "GND_P$6") (pintype "passive"))
      (node (ref "J2") (pin "GND") (pinfunction "GND_GND") (pintype "bidirectional"))
      (node (ref "J2") (pin "GNDBREAK") (pinfunction "GNDBREAK_GNDBREAK") (pintype "bidirectional"))
      (node (ref "J5") (pin "10") (pinfunction "10_10") (pintype "passive"))
      (node (ref "J5") (pin "9") (pinfunction "9_9") (pintype "passive"))
      (node (ref "J6") (pin "10") (pinfunction "10_10") (pintype "passive"))
      (node (ref "J6") (pin "9") (pinfunction "9_9") (pintype "passive"))
      (node (ref "JP3") (pin "3") (pinfunction "3_3") (pintype "passive"))
      (node (ref "JP4") (pin "3") (pinfunction "3_3") (pintype "passive"))
      (node (ref "JP5") (pin "4") (pinfunction "4_4") (pintype "passive"))
      (node (ref "JP6") (pin "4") (pinfunction "4_4") (pintype "passive"))
      (node (ref "OK1") (pin "4") (pinfunction "EMI_4") (pintype "passive"))
      (node (ref "OK2") (pin "4") (pinfunction "EMI_4") (pintype "passive"))
      (node (ref "OK3") (pin "4") (pinfunction "EMI_4") (pintype "passive"))
      (node (ref "OK4") (pin "4") (pinfunction "EMI_4") (pintype "passive"))
      (node (ref "OK5") (pin "4") (pinfunction "EMI_4") (pintype "passive"))
      (node (ref "R11") (pin "1") (pinfunction "1_1") (pintype "passive"))
      (node (ref "R15") (pin "1") (pinfunction "1_1") (pintype "passive"))
      (node (ref "R19") (pin "1") (pinfunction "1_1") (pintype "passive"))
      (node (ref "R22") (pin "2") (pinfunction "2_2") (pintype "passive"))
      (node (ref "R23") (pin "2") (pinfunction "2_2") (pintype "passive"))
      (node (ref "R24") (pin "2") (pinfunction "2_2") (pintype "passive"))
      (node (ref "R25") (pin "2") (pinfunction "2_2") (pintype "passive"))
      (node (ref "R3") (pin "1") (pinfunction "1_1") (pintype "passive"))
      (node (ref "R7") (pin "1") (pinfunction "1_1") (pintype "passive"))
      (node (ref "S1") (pin "3") (pinfunction "P_3") (pintype "passive"))
      (node (ref "T1") (pin "3") (pinfunction "E_3") (pintype "passive"))
      (node (ref "T2") (pin "3") (pinfunction "E_3") (pintype "passive"))
      (node (ref "T3") (pin "3") (pinfunction "E_3") (pintype "passive"))
      (node (ref "T4") (pin "3") (pinfunction "E_3") (pintype "passive"))
      (node (ref "T5") (pin "3") (pinfunction "E_3") (pintype "passive"))
      (node (ref "X1") (pin "13") (pinfunction "13_13") (pintype "passive"))
      (node (ref "X1") (pin "21") (pinfunction "21_21") (pintype "passive"))
      (node (ref "X1") (pin "4") (pinfunction "4_4") (pintype "passive"))
      (node (ref "X1") (pin "5") (pinfunction "5_5") (pintype "passive"))
      (node (ref "X1") (pin "9") (pinfunction "9_9") (pintype "passive"))
      (node (ref "X2") (pin "13") (pinfunction "13_13") (pintype "passive"))
      (node (ref "X2") (pin "21") (pinfunction "21_21") (pintype "passive"))
      (node (ref "X2") (pin "4") (pinfunction "4_4") (pintype "passive"))
      (node (ref "X2") (pin "5") (pinfunction "5_5") (pintype "passive"))
      (node (ref "X2") (pin "9") (pinfunction "9_9") (pintype "passive"))
      (node (ref "X3") (pin "13") (pinfunction "13_13") (pintype "passive"))
      (node (ref "X3") (pin "21") (pinfunction "21_21") (pintype "passive"))
      (node (ref "X3") (pin "4") (pinfunction "4_4") (pintype "passive"))
      (node (ref "X3") (pin "5") (pinfunction "5_5") (pintype "passive"))
      (node (ref "X3") (pin "9") (pinfunction "9_9") (pintype "passive"))
      (node (ref "X4") (pin "13") (pinfunction "13_13") (pintype "passive"))
      (node (ref "X4") (pin "21") (pinfunction "21_21") (pintype "passive"))
      (node (ref "X4") (pin "4") (pinfunction "4_4") (pintype "passive"))
      (node (ref "X4") (pin "5") (pinfunction "5_5") (pintype "passive"))
      (node (ref "X4") (pin "9") (pinfunction "9_9") (pintype "passive"))
      (node (ref "X5") (pin "13") (pinfunction "13_13") (pintype "passive"))
      (node (ref "X5") (pin "21") (pinfunction "21_21") (pintype "passive"))
      (node (ref "X5") (pin "4") (pinfunction "4_4") (pintype "passive"))
      (node (ref "X5") (pin "5") (pinfunction "5_5") (pintype "passive"))
      (node (ref "X5") (pin "9") (pinfunction "9_9") (pintype "passive"))
      (node (ref "X6") (pin "4") (pinfunction "4_4") (pintype "passive"))
      (node (ref "Y1") (pin "2") (pinfunction "2_2") (pintype "passive"))
    )
    (net (code "38") (name "GREEN-1") (class "Default")
      (node (ref "K2") (pin "S1") (pinfunction "S_S1") (pintype "passive"))
      (node (ref "X1") (pin "11") (pinfunction "11_11") (pintype "passive"))
    )
    (net (code "39") (name "GREEN-2") (class "Default")
      (node (ref "K5") (pin "S1") (pinfunction "S_S1") (pintype "passive"))
      (node (ref "X2") (pin "11") (pinfunction "11_11") (pintype "passive"))
    )
    (net (code "40") (name "GREEN-3") (class "Default")
      (node (ref "K8") (pin "S1") (pinfunction "S_S1") (pintype "passive"))
      (node (ref "X3") (pin "11") (pinfunction "11_11") (pintype "passive"))
    )
    (net (code "41") (name "GREEN-4") (class "Default")
      (node (ref "K11") (pin "S1") (pinfunction "S_S1") (pintype "passive"))
      (node (ref "X4") (pin "11") (pinfunction "11_11") (pintype "passive"))
    )
    (net (code "42") (name "GREEN-5") (class "Default")
      (node (ref "K14") (pin "S1") (pinfunction "S_S1") (pintype "passive"))
      (node (ref "X5") (pin "11") (pinfunction "11_11") (pintype "passive"))
    )
    (net (code "43") (name "GREEN_1") (class "Default")
      (node (ref "K2") (pin "P1") (pinfunction "P_P1") (pintype "passive"))
      (node (ref "K5") (pin "O1") (pinfunction "O_O1") (pintype "passive"))
    )
    (net (code "44") (name "GREEN_2") (class "Default")
      (node (ref "K5") (pin "P1") (pinfunction "P_P1") (pintype "passive"))
      (node (ref "K8") (pin "O1") (pinfunction "O_O1") (pintype "passive"))
    )
    (net (code "45") (name "GREEN_3") (class "Default")
      (node (ref "K11") (pin "O1") (pinfunction "O_O1") (pintype "passive"))
      (node (ref "K8") (pin "P1") (pinfunction "P_P1") (pintype "passive"))
    )
    (net (code "46") (name "GREEN_4") (class "Default")
      (node (ref "K11") (pin "P1") (pinfunction "P_P1") (pintype "passive"))
      (node (ref "K14") (pin "O1") (pinfunction "O_O1") (pintype "passive"))
    )
    (net (code "47") (name "GREEN_IN") (class "Default")
      (node (ref "J5") (pin "3") (pinfunction "3_3") (pintype "passive"))
      (node (ref "K2") (pin "O1") (pinfunction "O_O1") (pintype "passive"))
    )
    (net (code "48") (name "GREEN_OUT") (class "Default")
      (node (ref "J6") (pin "3") (pinfunction "3_3") (pintype "passive"))
      (node (ref "K14") (pin "P1") (pinfunction "P_P1") (pintype "passive"))
      (node (ref "X6") (pin "7") (pinfunction "7_7") (pintype "passive"))
    )
    (net (code "49") (name "Net-(D16-PadA)") (class "Default")
      (node (ref "D16") (pin "A") (pinfunction "A_A") (pintype "passive"))
      (node (ref "D17") (pin "A") (pinfunction "A_A") (pintype "passive"))
      (node (ref "J2") (pin "PWR") (pinfunction "PWR_PWR") (pintype "bidirectional"))
    )
    (net (code "50") (name "Net-(IC1-(PCI8{slash}ADC0)PC0)") (class "Default")
      (node (ref "IC1") (pin "23") (pinfunction "(PCI8/ADC0)PC0_23") (pintype "bidirectional"))
      (node (ref "R22") (pin "1") (pinfunction "1_1") (pintype "passive"))
      (node (ref "SW1") (pin "4") (pinfunction "4_4") (pintype "passive"))
    )
    (net (code "51") (name "Net-(IC1-(PCI9{slash}ADC1)PC1)") (class "Default")
      (node (ref "IC1") (pin "24") (pinfunction "(PCI9/ADC1)PC1_24") (pintype "bidirectional"))
      (node (ref "R23") (pin "1") (pinfunction "1_1") (pintype "passive"))
      (node (ref "SW1") (pin "5") (pinfunction "5_5") (pintype "passive"))
    )
    (net (code "52") (name "Net-(IC1-(PCI10{slash}ADC2)PC2)") (class "Default")
      (node (ref "IC1") (pin "25") (pinfunction "(PCI10/ADC2)PC2_25") (pintype "bidirectional"))
      (node (ref "R24") (pin "1") (pinfunction "1_1") (pintype "passive"))
      (node (ref "SW1") (pin "6") (pinfunction "6_6") (pintype "passive"))
    )
    (net (code "53") (name "Net-(IC1-(PCI11{slash}ADC3)PC3)") (class "Default")
      (node (ref "IC1") (pin "26") (pinfunction "(PCI11/ADC3)PC3_26") (pintype "bidirectional"))
      (node (ref "JP7") (pin "1") (pinfunction "1_1") (pintype "passive"))
      (node (ref "R25") (pin "1") (pinfunction "1_1") (pintype "passive"))
      (node (ref "S2") (pin "3") (pinfunction "P_3") (pintype "passive"))
    )
    (net (code "54") (name "Net-(IC1-(PCI12{slash}ADC4{slash}SDA)PC4)") (class "Default")
      (node (ref "IC1") (pin "27") (pinfunction "(PCI12/ADC4/SDA)PC4_27") (pintype "bidirectional"))
      (node (ref "JP5") (pin "2") (pinfunction "2_2") (pintype "passive"))
      (node (ref "JP6") (pin "2") (pinfunction "2_2") (pintype "passive"))
    )
    (net (code "55") (name "Net-(IC1-(PCI13{slash}ADC5{slash}SCL)PC5)") (class "Default")
      (node (ref "IC1") (pin "28") (pinfunction "(PCI13/ADC5/SCL)PC5_28") (pintype "bidirectional"))
      (node (ref "JP5") (pin "3") (pinfunction "3_3") (pintype "passive"))
      (node (ref "JP6") (pin "3") (pinfunction "3_3") (pintype "passive"))
    )
    (net (code "56") (name "Net-(IC1-(PCI16{slash}RXD)PD0)") (class "Default")
      (node (ref "IC1") (pin "2") (pinfunction "(PCI16/RXD)PD0_2") (pintype "bidirectional"))
      (node (ref "J1") (pin "P$2") (pinfunction "TXO_P$2") (pintype "passive"))
    )
    (net (code "57") (name "Net-(IC1-(PCI17{slash}TXD)PD1)") (class "Default")
      (node (ref "IC1") (pin "3") (pinfunction "(PCI17/TXD)PD1_3") (pintype "bidirectional"))
      (node (ref "J1") (pin "P$3") (pinfunction "RXI_P$3") (pintype "passive"))
    )
    (net (code "58") (name "Net-(IC1-PB6(XTAL1{slash}TOSC1{slash}PCI6))") (class "Default")
      (node (ref "IC1") (pin "9") (pinfunction "PB6(XTAL1/TOSC1/PCI6)_9") (pintype "bidirectional"))
      (node (ref "Y1") (pin "1") (pinfunction "1_1") (pintype "passive"))
    )
    (net (code "59") (name "Net-(IC1-PB7(XTAL2{slash}TOSC2{slash}PCI7))") (class "Default")
      (node (ref "IC1") (pin "10") (pinfunction "PB7(XTAL2/TOSC2/PCI7)_10") (pintype "bidirectional"))
      (node (ref "Y1") (pin "3") (pinfunction "3_3") (pintype "passive"))
    )
    (net (code "60") (name "Net-(J1-DTR)") (class "Default")
      (node (ref "C1") (pin "2") (pinfunction "2_2") (pintype "passive"))
      (node (ref "J1") (pin "P$1") (pinfunction "DTR_P$1") (pintype "passive"))
    )
    (net (code "61") (name "Net-(K1A-2)") (class "Default")
      (node (ref "D1") (pin "A") (pinfunction "A_A") (pintype "passive"))
      (node (ref "D2") (pin "A") (pinfunction "A_A") (pintype "passive"))
      (node (ref "D3") (pin "A") (pinfunction "A_A") (pintype "passive"))
      (node (ref "K1") (pin "16") (pinfunction "2_16") (pintype "passive"))
      (node (ref "K2") (pin "16") (pinfunction "2_16") (pintype "passive"))
      (node (ref "K3") (pin "16") (pinfunction "2_16") (pintype "passive"))
      (node (ref "LED1") (pin "K") (pinfunction "C_K") (pintype "passive"))
      (node (ref "T1") (pin "2") (pinfunction "C_2") (pintype "passive"))
    )
    (net (code "62") (name "Net-(K4A-2)") (class "Default")
      (node (ref "D4") (pin "A") (pinfunction "A_A") (pintype "passive"))
      (node (ref "D5") (pin "A") (pinfunction "A_A") (pintype "passive"))
      (node (ref "D6") (pin "A") (pinfunction "A_A") (pintype "passive"))
      (node (ref "K4") (pin "16") (pinfunction "2_16") (pintype "passive"))
      (node (ref "K5") (pin "16") (pinfunction "2_16") (pintype "passive"))
      (node (ref "K6") (pin "16") (pinfunction "2_16") (pintype "passive"))
      (node (ref "LED2") (pin "K") (pinfunction "C_K") (pintype "passive"))
      (node (ref "T2") (pin "2") (pinfunction "C_2") (pintype "passive"))
    )
    (net (code "63") (name "Net-(K7A-2)") (class "Default")
      (node (ref "D7") (pin "A") (pinfunction "A_A") (pintype "passive"))
      (node (ref "D8") (pin "A") (pinfunction "A_A") (pintype "passive"))
      (node (ref "D9") (pin "A") (pinfunction "A_A") (pintype "passive"))
      (node (ref "K7") (pin "16") (pinfunction "2_16") (pintype "passive"))
      (node (ref "K8") (pin "16") (pinfunction "2_16") (pintype "passive"))
      (node (ref "K9") (pin "16") (pinfunction "2_16") (pintype "passive"))
      (node (ref "LED3") (pin "K") (pinfunction "C_K") (pintype "passive"))
      (node (ref "T3") (pin "2") (pinfunction "C_2") (pintype "passive"))
    )
    (net (code "64") (name "Net-(K10A-2)") (class "Default")
      (node (ref "D10") (pin "A") (pinfunction "A_A") (pintype "passive"))
      (node (ref "D11") (pin "A") (pinfunction "A_A") (pintype "passive"))
      (node (ref "D12") (pin "A") (pinfunction "A_A") (pintype "passive"))
      (node (ref "K10") (pin "16") (pinfunction "2_16") (pintype "passive"))
      (node (ref "K11") (pin "16") (pinfunction "2_16") (pintype "passive"))
      (node (ref "K12") (pin "16") (pinfunction "2_16") (pintype "passive"))
      (node (ref "LED4") (pin "K") (pinfunction "C_K") (pintype "passive"))
      (node (ref "T4") (pin "2") (pinfunction "C_2") (pintype "passive"))
    )
    (net (code "65") (name "Net-(K13A-2)") (class "Default")
      (node (ref "D13") (pin "A") (pinfunction "A_A") (pintype "passive"))
      (node (ref "D14") (pin "A") (pinfunction "A_A") (pintype "passive"))
      (node (ref "D15") (pin "A") (pinfunction "A_A") (pintype "passive"))
      (node (ref "K13") (pin "16") (pinfunction "2_16") (pintype "passive"))
      (node (ref "K14") (pin "16") (pinfunction "2_16") (pintype "passive"))
      (node (ref "K15") (pin "16") (pinfunction "2_16") (pintype "passive"))
      (node (ref "LED5") (pin "K") (pinfunction "C_K") (pintype "passive"))
      (node (ref "T5") (pin "2") (pinfunction "C_2") (pintype "passive"))
    )
    (net (code "66") (name "Net-(LED1-PadA)") (class "Default")
      (node (ref "LED1") (pin "A") (pinfunction "A_A") (pintype "passive"))
      (node (ref "R2") (pin "1") (pinfunction "1_1") (pintype "passive"))
    )
    (net (code "67") (name "Net-(LED2-PadA)") (class "Default")
      (node (ref "LED2") (pin "A") (pinfunction "A_A") (pintype "passive"))
      (node (ref "R6") (pin "1") (pinfunction "1_1") (pintype "passive"))
    )
    (net (code "68") (name "Net-(LED3-PadA)") (class "Default")
      (node (ref "LED3") (pin "A") (pinfunction "A_A") (pintype "passive"))
      (node (ref "R10") (pin "1") (pinfunction "1_1") (pintype "passive"))
    )
    (net (code "69") (name "Net-(LED4-PadA)") (class "Default")
      (node (ref "LED4") (pin "A") (pinfunction "A_A") (pintype "passive"))
      (node (ref "R14") (pin "1") (pinfunction "1_1") (pintype "passive"))
    )
    (net (code "70") (name "Net-(LED5-PadA)") (class "Default")
      (node (ref "LED5") (pin "A") (pinfunction "A_A") (pintype "passive"))
      (node (ref "R18") (pin "1") (pinfunction "1_1") (pintype "passive"))
    )
    (net (code "71") (name "Net-(OK1-A)") (class "Default")
      (node (ref "D18") (pin "C") (pinfunction "C_C") (pintype "passive"))
      (node (ref "OK1") (pin "1") (pinfunction "A_1") (pintype "passive"))
      (node (ref "R26") (pin "2") (pinfunction "2_2") (pintype "passive"))
    )
    (net (code "72") (name "Net-(OK1-C)") (class "Default")
      (node (ref "OK1") (pin "2") (pinfunction "C_2") (pintype "passive"))
      (node (ref "R3") (pin "2") (pinfunction "2_2") (pintype "passive"))
    )
    (net (code "73") (name "Net-(OK2-A)") (class "Default")
      (node (ref "D19") (pin "C") (pinfunction "C_C") (pintype "passive"))
      (node (ref "OK2") (pin "1") (pinfunction "A_1") (pintype "passive"))
      (node (ref "R27") (pin "2") (pinfunction "2_2") (pintype "passive"))
    )
    (net (code "74") (name "Net-(OK2-C)") (class "Default")
      (node (ref "OK2") (pin "2") (pinfunction "C_2") (pintype "passive"))
      (node (ref "R7") (pin "2") (pinfunction "2_2") (pintype "passive"))
    )
    (net (code "75") (name "Net-(OK3-A)") (class "Default")
      (node (ref "D20") (pin "C") (pinfunction "C_C") (pintype "passive"))
      (node (ref "OK3") (pin "1") (pinfunction "A_1") (pintype "passive"))
      (node (ref "R28") (pin "2") (pinfunction "2_2") (pintype "passive"))
    )
    (net (code "76") (name "Net-(OK3-C)") (class "Default")
      (node (ref "OK3") (pin "2") (pinfunction "C_2") (pintype "passive"))
      (node (ref "R11") (pin "2") (pinfunction "2_2") (pintype "passive"))
    )
    (net (code "77") (name "Net-(OK4-A)") (class "Default")
      (node (ref "D21") (pin "C") (pinfunction "C_C") (pintype "passive"))
      (node (ref "OK4") (pin "1") (pinfunction "A_1") (pintype "passive"))
      (node (ref "R29") (pin "2") (pinfunction "2_2") (pintype "passive"))
    )
    (net (code "78") (name "Net-(OK4-C)") (class "Default")
      (node (ref "OK4") (pin "2") (pinfunction "C_2") (pintype "passive"))
      (node (ref "R15") (pin "2") (pinfunction "2_2") (pintype "passive"))
    )
    (net (code "79") (name "Net-(OK5-A)") (class "Default")
      (node (ref "D22") (pin "C") (pinfunction "C_C") (pintype "passive"))
      (node (ref "OK5") (pin "1") (pinfunction "A_1") (pintype "passive"))
      (node (ref "R30") (pin "2") (pinfunction "2_2") (pintype "passive"))
    )
    (net (code "80") (name "Net-(OK5-C)") (class "Default")
      (node (ref "OK5") (pin "2") (pinfunction "C_2") (pintype "passive"))
      (node (ref "R19") (pin "2") (pinfunction "2_2") (pintype "passive"))
    )
    (net (code "81") (name "Net-(R26-Pad1)") (class "Default")
      (node (ref "R26") (pin "1") (pinfunction "1_1") (pintype "passive"))
      (node (ref "X1") (pin "8") (pinfunction "8_8") (pintype "passive"))
    )
    (net (code "82") (name "Net-(R27-Pad1)") (class "Default")
      (node (ref "R27") (pin "1") (pinfunction "1_1") (pintype "passive"))
      (node (ref "X2") (pin "8") (pinfunction "8_8") (pintype "passive"))
    )
    (net (code "83") (name "Net-(R28-Pad1)") (class "Default")
      (node (ref "R28") (pin "1") (pinfunction "1_1") (pintype "passive"))
      (node (ref "X3") (pin "8") (pinfunction "8_8") (pintype "passive"))
    )
    (net (code "84") (name "Net-(R29-Pad1)") (class "Default")
      (node (ref "R29") (pin "1") (pinfunction "1_1") (pintype "passive"))
      (node (ref "X4") (pin "8") (pinfunction "8_8") (pintype "passive"))
    )
    (net (code "85") (name "Net-(R30-Pad1)") (class "Default")
      (node (ref "R30") (pin "1") (pinfunction "1_1") (pintype "passive"))
      (node (ref "X5") (pin "8") (pinfunction "8_8") (pintype "passive"))
    )
    (net (code "86") (name "Net-(T1-B)") (class "Default")
      (node (ref "R1") (pin "2") (pinfunction "2_2") (pintype "passive"))
      (node (ref "T1") (pin "1") (pinfunction "B_1") (pintype "passive"))
    )
    (net (code "87") (name "Net-(T2-B)") (class "Default")
      (node (ref "R5") (pin "2") (pinfunction "2_2") (pintype "passive"))
      (node (ref "T2") (pin "1") (pinfunction "B_1") (pintype "passive"))
    )
    (net (code "88") (name "Net-(T3-B)") (class "Default")
      (node (ref "R9") (pin "2") (pinfunction "2_2") (pintype "passive"))
      (node (ref "T3") (pin "1") (pinfunction "B_1") (pintype "passive"))
    )
    (net (code "89") (name "Net-(T4-B)") (class "Default")
      (node (ref "R13") (pin "2") (pinfunction "2_2") (pintype "passive"))
      (node (ref "T4") (pin "1") (pinfunction "B_1") (pintype "passive"))
    )
    (net (code "90") (name "Net-(T5-B)") (class "Default")
      (node (ref "R17") (pin "2") (pinfunction "2_2") (pintype "passive"))
      (node (ref "T5") (pin "1") (pinfunction "B_1") (pintype "passive"))
    )
    (net (code "91") (name "RED-1") (class "Default")
      (node (ref "K3") (pin "S2") (pinfunction "S_S2") (pintype "passive"))
      (node (ref "X1") (pin "15") (pinfunction "15_15") (pintype "passive"))
    )
    (net (code "92") (name "RED-2") (class "Default")
      (node (ref "K6") (pin "S2") (pinfunction "S_S2") (pintype "passive"))
      (node (ref "X2") (pin "15") (pinfunction "15_15") (pintype "passive"))
    )
    (net (code "93") (name "RED-3") (class "Default")
      (node (ref "K9") (pin "S2") (pinfunction "S_S2") (pintype "passive"))
      (node (ref "X3") (pin "15") (pinfunction "15_15") (pintype "passive"))
    )
    (net (code "94") (name "RED-4") (class "Default")
      (node (ref "K12") (pin "S2") (pinfunction "S_S2") (pintype "passive"))
      (node (ref "X4") (pin "15") (pinfunction "15_15") (pintype "passive"))
    )
    (net (code "95") (name "RED-5") (class "Default")
      (node (ref "K15") (pin "S2") (pinfunction "S_S2") (pintype "passive"))
      (node (ref "X5") (pin "15") (pinfunction "15_15") (pintype "passive"))
    )
    (net (code "96") (name "RED_1") (class "Default")
      (node (ref "K3") (pin "P2") (pinfunction "P_P2") (pintype "passive"))
      (node (ref "K6") (pin "O2") (pinfunction "O_O2") (pintype "passive"))
    )
    (net (code "97") (name "RED_2") (class "Default")
      (node (ref "K6") (pin "P2") (pinfunction "P_P2") (pintype "passive"))
      (node (ref "K9") (pin "O2") (pinfunction "O_O2") (pintype "passive"))
    )
    (net (code "98") (name "RED_3") (class "Default")
      (node (ref "K12") (pin "O2") (pinfunction "O_O2") (pintype "passive"))
      (node (ref "K9") (pin "P2") (pinfunction "P_P2") (pintype "passive"))
    )
    (net (code "99") (name "RED_4") (class "Default")
      (node (ref "K12") (pin "P2") (pinfunction "P_P2") (pintype "passive"))
      (node (ref "K15") (pin "O2") (pinfunction "O_O2") (pintype "passive"))
    )
    (net (code "100") (name "RED_IN") (class "Default")
      (node (ref "J5") (pin "1") (pinfunction "1_1") (pintype "passive"))
      (node (ref "K3") (pin "O2") (pinfunction "O_O2") (pintype "passive"))
    )
    (net (code "101") (name "RED_OUT") (class "Default")
      (node (ref "J6") (pin "1") (pinfunction "1_1") (pintype "passive"))
      (node (ref "K15") (pin "P2") (pinfunction "P_P2") (pintype "passive"))
      (node (ref "X6") (pin "8") (pinfunction "8_8") (pintype "passive"))
    )
    (net (code "102") (name "RESET") (class "Default")
      (node (ref "C1") (pin "1") (pinfunction "1_1") (pintype "passive"))
      (node (ref "IC1") (pin "1") (pinfunction "PC6(/RESET/PCI14)_1") (pintype "bidirectional"))
      (node (ref "R21") (pin "1") (pinfunction "1_1") (pintype "passive"))
      (node (ref "S1") (pin "1") (pinfunction "S_1") (pintype "passive"))
    )
    (net (code "103") (name "R_1") (class "Default")
      (node (ref "IC1") (pin "14") (pinfunction "(PCI0/ICP/CLKO)PB0_14") (pintype "bidirectional"))
      (node (ref "R1") (pin "1") (pinfunction "1_1") (pintype "passive"))
    )
    (net (code "104") (name "R_2") (class "Default")
      (node (ref "IC1") (pin "15") (pinfunction "(PCI1/OC1A/OC1S)PB1_15") (pintype "bidirectional"))
      (node (ref "R5") (pin "1") (pinfunction "1_1") (pintype "passive"))
    )
    (net (code "105") (name "R_3") (class "Default")
      (node (ref "IC1") (pin "16") (pinfunction "(PCI2/SS/OC1B)PB2_16") (pintype "bidirectional"))
      (node (ref "R9") (pin "1") (pinfunction "1_1") (pintype "passive"))
    )
    (net (code "106") (name "R_4") (class "Default")
      (node (ref "IC1") (pin "17") (pinfunction "(PCI3/MOSI/OC2A)PB3_17") (pintype "bidirectional"))
      (node (ref "R13") (pin "1") (pinfunction "1_1") (pintype "passive"))
    )
    (net (code "107") (name "R_5") (class "Default")
      (node (ref "IC1") (pin "18") (pinfunction "(PCI4/MISO)PB4_18") (pintype "bidirectional"))
      (node (ref "R17") (pin "1") (pinfunction "1_1") (pintype "passive"))
    )
    (net (code "108") (name "R_EXT") (class "Default")
      (node (ref "IC1") (pin "19") (pinfunction "(PCI5/SCK)PB5_19") (pintype "bidirectional"))
    )
    (net (code "109") (name "SYNC-1") (class "Default")
      (node (ref "K3") (pin "S1") (pinfunction "S_S1") (pintype "passive"))
      (node (ref "X1") (pin "20") (pinfunction "20_20") (pintype "passive"))
    )
    (net (code "110") (name "SYNC-2") (class "Default")
      (node (ref "K6") (pin "S1") (pinfunction "S_S1") (pintype "passive"))
      (node (ref "X2") (pin "20") (pinfunction "20_20") (pintype "passive"))
    )
    (net (code "111") (name "SYNC-3") (class "Default")
      (node (ref "K9") (pin "S1") (pinfunction "S_S1") (pintype "passive"))
      (node (ref "X3") (pin "20") (pinfunction "20_20") (pintype "passive"))
    )
    (net (code "112") (name "SYNC-4") (class "Default")
      (node (ref "K12") (pin "S1") (pinfunction "S_S1") (pintype "passive"))
      (node (ref "X4") (pin "20") (pinfunction "20_20") (pintype "passive"))
    )
    (net (code "113") (name "SYNC-5") (class "Default")
      (node (ref "K15") (pin "S1") (pinfunction "S_S1") (pintype "passive"))
      (node (ref "X5") (pin "20") (pinfunction "20_20") (pintype "passive"))
    )
    (net (code "114") (name "SYNC_1") (class "Default")
      (node (ref "K3") (pin "P1") (pinfunction "P_P1") (pintype "passive"))
      (node (ref "K6") (pin "O1") (pinfunction "O_O1") (pintype "passive"))
    )
    (net (code "115") (name "SYNC_2") (class "Default")
      (node (ref "K6") (pin "P1") (pinfunction "P_P1") (pintype "passive"))
      (node (ref "K9") (pin "O1") (pinfunction "O_O1") (pintype "passive"))
    )
    (net (code "116") (name "SYNC_3") (class "Default")
      (node (ref "K12") (pin "O1") (pinfunction "O_O1") (pintype "passive"))
      (node (ref "K9") (pin "P1") (pinfunction "P_P1") (pintype "passive"))
    )
    (net (code "117") (name "SYNC_4") (class "Default")
      (node (ref "K12") (pin "P1") (pinfunction "P_P1") (pintype "passive"))
      (node (ref "K15") (pin "O1") (pinfunction "O_O1") (pintype "passive"))
    )
    (net (code "118") (name "SYNC_IN") (class "Default")
      (node (ref "J5") (pin "7") (pinfunction "7_7") (pintype "passive"))
      (node (ref "K3") (pin "O1") (pinfunction "O_O1") (pintype "passive"))
    )
    (net (code "119") (name "SYNC_OUT") (class "Default")
      (node (ref "J6") (pin "7") (pinfunction "7_7") (pintype "passive"))
      (node (ref "K15") (pin "P1") (pinfunction "P_P1") (pintype "passive"))
      (node (ref "X6") (pin "3") (pinfunction "3_3") (pintype "passive"))
    )
    (net (code "120") (name "S_1") (class "Default")
      (node (ref "IC1") (pin "4") (pinfunction "(PCI18/INT0)PD2_4") (pintype "bidirectional"))
      (node (ref "OK1") (pin "5") (pinfunction "COL_5") (pintype "passive"))
      (node (ref "R4") (pin "1") (pinfunction "1_1") (pintype "passive"))
    )
    (net (code "121") (name "S_2") (class "Default")
      (node (ref "IC1") (pin "5") (pinfunction "(PCI19/INT1/OC2B)PD3_5") (pintype "bidirectional"))
      (node (ref "OK2") (pin "5") (pinfunction "COL_5") (pintype "passive"))
      (node (ref "R8") (pin "1") (pinfunction "1_1") (pintype "passive"))
    )
    (net (code "122") (name "S_3") (class "Default")
      (node (ref "IC1") (pin "6") (pinfunction "(PCI20/XCK/T0)PD4_6") (pintype "bidirectional"))
      (node (ref "OK3") (pin "5") (pinfunction "COL_5") (pintype "passive"))
      (node (ref "R12") (pin "1") (pinfunction "1_1") (pintype "passive"))
    )
    (net (code "123") (name "S_4") (class "Default")
      (node (ref "IC1") (pin "11") (pinfunction "(PCI21/T1/OC0B)PD5_11") (pintype "bidirectional"))
      (node (ref "OK4") (pin "5") (pinfunction "COL_5") (pintype "passive"))
      (node (ref "R16") (pin "1") (pinfunction "1_1") (pintype "passive"))
    )
    (net (code "124") (name "S_5") (class "Default")
      (node (ref "IC1") (pin "12") (pinfunction "(PCI22/AIN0OC0A)PD6_12") (pintype "bidirectional"))
      (node (ref "OK5") (pin "5") (pinfunction "COL_5") (pintype "passive"))
      (node (ref "R20") (pin "1") (pinfunction "1_1") (pintype "passive"))
    )
    (net (code "125") (name "S_EXT") (class "Default")
      (node (ref "IC1") (pin "13") (pinfunction "(PCI23/AIN1)PD7_13") (pintype "bidirectional"))
    )
    (net (code "126") (name "unconnected-(IC1-AREF-Pad21)") (class "Default")
      (node (ref "IC1") (pin "21") (pinfunction "AREF_21") (pintype "bidirectional"))
    )
    (net (code "127") (name "unconnected-(J1-CTS-PadP$5)") (class "Default")
      (node (ref "J1") (pin "P$5") (pinfunction "CTS_P$5") (pintype "passive"))
    )
    (net (code "128") (name "unconnected-(JP3-Pad2)") (class "Default")
      (node (ref "JP3") (pin "2") (pinfunction "2_2") (pintype "passive"))
    )
    (net (code "129") (name "unconnected-(JP4-Pad2)") (class "Default")
      (node (ref "JP4") (pin "2") (pinfunction "2_2") (pintype "passive"))
    )
    (net (code "130") (name "unconnected-(K2C-P-PadP2)") (class "Default")
      (node (ref "K2") (pin "P2") (pinfunction "P_P2") (pintype "passive"))
    )
    (net (code "131") (name "unconnected-(K4B-S-PadS1)") (class "Default")
      (node (ref "K4") (pin "S1") (pinfunction "S_S1") (pintype "passive"))
    )
    (net (code "132") (name "unconnected-(K5C-S-PadS2)") (class "Default")
      (node (ref "K5") (pin "S2") (pinfunction "S_S2") (pintype "passive"))
    )
    (net (code "133") (name "unconnected-(OK1-BAS-Pad6)") (class "Default")
      (node (ref "OK1") (pin "6") (pinfunction "BAS_6") (pintype "passive"))
    )
    (net (code "134") (name "unconnected-(OK2-BAS-Pad6)") (class "Default")
      (node (ref "OK2") (pin "6") (pinfunction "BAS_6") (pintype "passive"))
    )
    (net (code "135") (name "unconnected-(OK3-BAS-Pad6)") (class "Default")
      (node (ref "OK3") (pin "6") (pinfunction "BAS_6") (pintype "passive"))
    )
    (net (code "136") (name "unconnected-(OK4-BAS-Pad6)") (class "Default")
      (node (ref "OK4") (pin "6") (pinfunction "BAS_6") (pintype "passive"))
    )
    (net (code "137") (name "unconnected-(OK5-BAS-Pad6)") (class "Default")
      (node (ref "OK5") (pin "6") (pinfunction "BAS_6") (pintype "passive"))
    )
    (net (code "138") (name "unconnected-(S1-P1-Pad4)") (class "Default")
      (node (ref "S1") (pin "4") (pinfunction "P1_4") (pintype "passive"))
    )
    (net (code "139") (name "unconnected-(S1-S1-Pad2)") (class "Default")
      (node (ref "S1") (pin "2") (pinfunction "S1_2") (pintype "passive"))
    )
    (net (code "140") (name "unconnected-(S2-P1-Pad4)") (class "Default")
      (node (ref "S2") (pin "4") (pinfunction "P1_4") (pintype "passive"))
    )
    (net (code "141") (name "unconnected-(S2-S1-Pad2)") (class "Default")
      (node (ref "S2") (pin "2") (pinfunction "S1_2") (pintype "passive"))
    )
    (net (code "142") (name "unconnected-(X1-Pad1)") (class "Default")
      (node (ref "X1") (pin "1") (pinfunction "1_1") (pintype "passive"))
    )
    (net (code "143") (name "unconnected-(X1-Pad3)") (class "Default")
      (node (ref "X1") (pin "3") (pinfunction "3_3") (pintype "passive"))
    )
    (net (code "144") (name "unconnected-(X1-Pad10)") (class "Default")
      (node (ref "X1") (pin "10") (pinfunction "10_10") (pintype "passive"))
    )
    (net (code "145") (name "unconnected-(X1-Pad12)") (class "Default")
      (node (ref "X1") (pin "12") (pinfunction "12_12") (pintype "passive"))
    )
    (net (code "146") (name "unconnected-(X1-Pad14)") (class "Default")
      (node (ref "X1") (pin "14") (pinfunction "14_14") (pintype "passive"))
    )
    (net (code "147") (name "unconnected-(X1-Pad16)") (class "Default")
      (node (ref "X1") (pin "16") (pinfunction "16_16") (pintype "passive"))
    )
    (net (code "148") (name "unconnected-(X1-Pad17)") (class "Default")
      (node (ref "X1") (pin "17") (pinfunction "17_17") (pintype "passive"))
    )
    (net (code "149") (name "unconnected-(X1-Pad18)") (class "Default")
      (node (ref "X1") (pin "18") (pinfunction "18_18") (pintype "passive"))
    )
    (net (code "150") (name "unconnected-(X1-Pad19)") (class "Default")
      (node (ref "X1") (pin "19") (pinfunction "19_19") (pintype "passive"))
    )
    (net (code "151") (name "unconnected-(X2-Pad1)") (class "Default")
      (node (ref "X2") (pin "1") (pinfunction "1_1") (pintype "passive"))
    )
    (net (code "152") (name "unconnected-(X2-Pad3)") (class "Default")
      (node (ref "X2") (pin "3") (pinfunction "3_3") (pintype "passive"))
    )
    (net (code "153") (name "unconnected-(X2-Pad10)") (class "Default")
      (node (ref "X2") (pin "10") (pinfunction "10_10") (pintype "passive"))
    )
    (net (code "154") (name "unconnected-(X2-Pad12)") (class "Default")
      (node (ref "X2") (pin "12") (pinfunction "12_12") (pintype "passive"))
    )
    (net (code "155") (name "unconnected-(X2-Pad14)") (class "Default")
      (node (ref "X2") (pin "14") (pinfunction "14_14") (pintype "passive"))
    )
    (net (code "156") (name "unconnected-(X2-Pad16)") (class "Default")
      (node (ref "X2") (pin "16") (pinfunction "16_16") (pintype "passive"))
    )
    (net (code "157") (name "unconnected-(X2-Pad17)") (class "Default")
      (node (ref "X2") (pin "17") (pinfunction "17_17") (pintype "passive"))
    )
    (net (code "158") (name "unconnected-(X2-Pad18)") (class "Default")
      (node (ref "X2") (pin "18") (pinfunction "18_18") (pintype "passive"))
    )
    (net (code "159") (name "unconnected-(X2-Pad19)") (class "Default")
      (node (ref "X2") (pin "19") (pinfunction "19_19") (pintype "passive"))
    )
    (net (code "160") (name "unconnected-(X3-Pad1)") (class "Default")
      (node (ref "X3") (pin "1") (pinfunction "1_1") (pintype "passive"))
    )
    (net (code "161") (name "unconnected-(X3-Pad3)") (class "Default")
      (node (ref "X3") (pin "3") (pinfunction "3_3") (pintype "passive"))
    )
    (net (code "162") (name "unconnected-(X3-Pad10)") (class "Default")
      (node (ref "X3") (pin "10") (pinfunction "10_10") (pintype "passive"))
    )
    (net (code "163") (name "unconnected-(X3-Pad12)") (class "Default")
      (node (ref "X3") (pin "12") (pinfunction "12_12") (pintype "passive"))
    )
    (net (code "164") (name "unconnected-(X3-Pad14)") (class "Default")
      (node (ref "X3") (pin "14") (pinfunction "14_14") (pintype "passive"))
    )
    (net (code "165") (name "unconnected-(X3-Pad16)") (class "Default")
      (node (ref "X3") (pin "16") (pinfunction "16_16") (pintype "passive"))
    )
    (net (code "166") (name "unconnected-(X3-Pad17)") (class "Default")
      (node (ref "X3") (pin "17") (pinfunction "17_17") (pintype "passive"))
    )
    (net (code "167") (name "unconnected-(X3-Pad18)") (class "Default")
      (node (ref "X3") (pin "18") (pinfunction "18_18") (pintype "passive"))
    )
    (net (code "168") (name "unconnected-(X3-Pad19)") (class "Default")
      (node (ref "X3") (pin "19") (pinfunction "19_19") (pintype "passive"))
    )
    (net (code "169") (name "unconnected-(X4-Pad1)") (class "Default")
      (node (ref "X4") (pin "1") (pinfunction "1_1") (pintype "passive"))
    )
    (net (code "170") (name "unconnected-(X4-Pad3)") (class "Default")
      (node (ref "X4") (pin "3") (pinfunction "3_3") (pintype "passive"))
    )
    (net (code "171") (name "unconnected-(X4-Pad10)") (class "Default")
      (node (ref "X4") (pin "10") (pinfunction "10_10") (pintype "passive"))
    )
    (net (code "172") (name "unconnected-(X4-Pad12)") (class "Default")
      (node (ref "X4") (pin "12") (pinfunction "12_12") (pintype "passive"))
    )
    (net (code "173") (name "unconnected-(X4-Pad14)") (class "Default")
      (node (ref "X4") (pin "14") (pinfunction "14_14") (pintype "passive"))
    )
    (net (code "174") (name "unconnected-(X4-Pad16)") (class "Default")
      (node (ref "X4") (pin "16") (pinfunction "16_16") (pintype "passive"))
    )
    (net (code "175") (name "unconnected-(X4-Pad17)") (class "Default")
      (node (ref "X4") (pin "17") (pinfunction "17_17") (pintype "passive"))
    )
    (net (code "176") (name "unconnected-(X4-Pad18)") (class "Default")
      (node (ref "X4") (pin "18") (pinfunction "18_18") (pintype "passive"))
    )
    (net (code "177") (name "unconnected-(X4-Pad19)") (class "Default")
      (node (ref "X4") (pin "19") (pinfunction "19_19") (pintype "passive"))
    )
    (net (code "178") (name "unconnected-(X5-Pad1)") (class "Default")
      (node (ref "X5") (pin "1") (pinfunction "1_1") (pintype "passive"))
    )
    (net (code "179") (name "unconnected-(X5-Pad3)") (class "Default")
      (node (ref "X5") (pin "3") (pinfunction "3_3") (pintype "passive"))
    )
    (net (code "180") (name "unconnected-(X5-Pad10)") (class "Default")
      (node (ref "X5") (pin "10") (pinfunction "10_10") (pintype "passive"))
    )
    (net (code "181") (name "unconnected-(X5-Pad12)") (class "Default")
      (node (ref "X5") (pin "12") (pinfunction "12_12") (pintype "passive"))
    )
    (net (code "182") (name "unconnected-(X5-Pad14)") (class "Default")
      (node (ref "X5") (pin "14") (pinfunction "14_14") (pintype "passive"))
    )
    (net (code "183") (name "unconnected-(X5-Pad16)") (class "Default")
      (node (ref "X5") (pin "16") (pinfunction "16_16") (pintype "passive"))
    )
    (net (code "184") (name "unconnected-(X5-Pad17)") (class "Default")
      (node (ref "X5") (pin "17") (pinfunction "17_17") (pintype "passive"))
    )
    (net (code "185") (name "unconnected-(X5-Pad18)") (class "Default")
      (node (ref "X5") (pin "18") (pinfunction "18_18") (pintype "passive"))
    )
    (net (code "186") (name "unconnected-(X5-Pad19)") (class "Default")
      (node (ref "X5") (pin "19") (pinfunction "19_19") (pintype "passive"))
    )
  )
)
